# zynq.net
KiCad netlist of a schematic drawn in Altium Designer
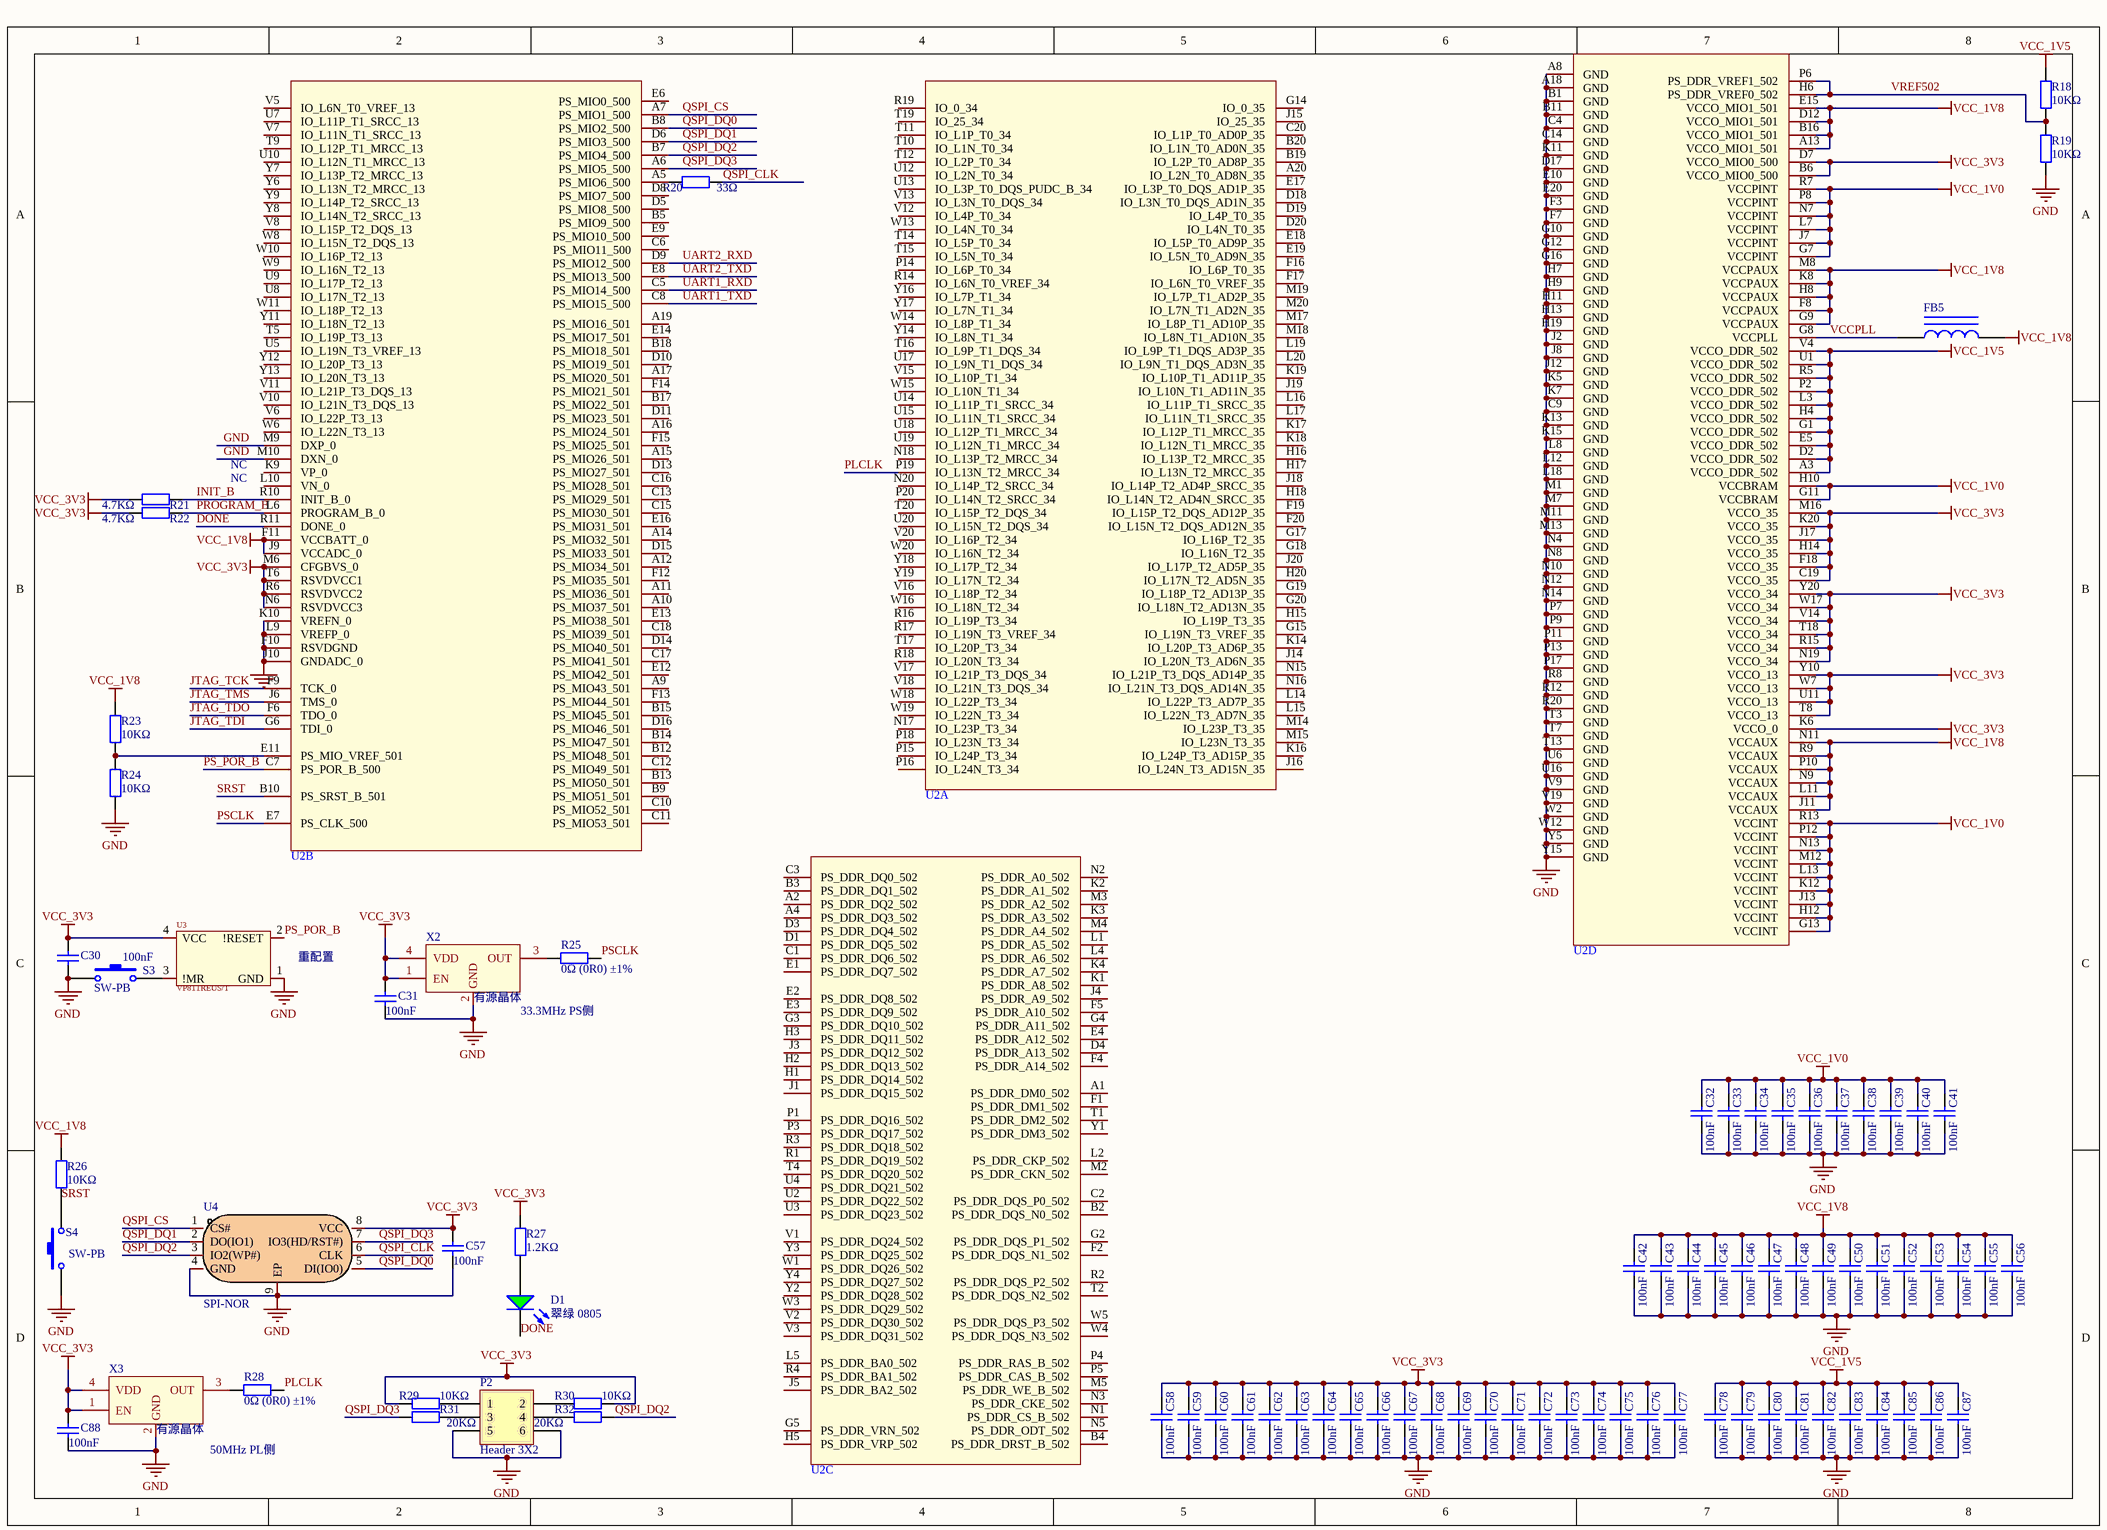
[diagram p0: zynq.SchDoc]

(export (version "E")
  (design (tool "Eeschema 10.0.6"))
  (components
    (comp (ref "C30")
      (value "100nF")
      (footprint "0805_C")
      (description "贴片电容")
      (libsource (lib "Miscellaneous Devices LC") (part "0402 100nF (104) 10% 16V"))
    )
    (comp (ref "C31")
      (value "100nF")
      (footprint "0805_C")
      (description "贴片电容")
      (libsource (lib "Miscellaneous Devices LC") (part "0402 100nF (104) 10% 16V"))
    )
    (comp (ref "C32")
      (value "100nF")
      (footprint "0201")
      (description "贴片电容")
      (libsource (lib "Miscellaneous Devices LC") (part "0402 100nF (104) 10% 16V"))
    )
    (comp (ref "C33")
      (value "100nF")
      (footprint "0201")
      (description "贴片电容")
      (libsource (lib "Miscellaneous Devices LC") (part "0402 100nF (104) 10% 16V"))
    )
    (comp (ref "C34")
      (value "100nF")
      (footprint "0201")
      (description "贴片电容")
      (libsource (lib "Miscellaneous Devices LC") (part "0402 100nF (104) 10% 16V"))
    )
    (comp (ref "C35")
      (value "100nF")
      (footprint "0201")
      (description "贴片电容")
      (libsource (lib "Miscellaneous Devices LC") (part "0402 100nF (104) 10% 16V"))
    )
    (comp (ref "C36")
      (value "100nF")
      (footprint "0201")
      (description "贴片电容")
      (libsource (lib "Miscellaneous Devices LC") (part "0402 100nF (104) 10% 16V"))
    )
    (comp (ref "C37")
      (value "100nF")
      (footprint "0201")
      (description "贴片电容")
      (libsource (lib "Miscellaneous Devices LC") (part "0402 100nF (104) 10% 16V"))
    )
    (comp (ref "C38")
      (value "100nF")
      (footprint "0201")
      (description "贴片电容")
      (libsource (lib "Miscellaneous Devices LC") (part "0402 100nF (104) 10% 16V"))
    )
    (comp (ref "C39")
      (value "100nF")
      (footprint "0201")
      (description "贴片电容")
      (libsource (lib "Miscellaneous Devices LC") (part "0402 100nF (104) 10% 16V"))
    )
    (comp (ref "C40")
      (value "100nF")
      (footprint "0201")
      (description "贴片电容")
      (libsource (lib "Miscellaneous Devices LC") (part "0402 100nF (104) 10% 16V"))
    )
    (comp (ref "C41")
      (value "100nF")
      (footprint "0201")
      (description "贴片电容")
      (libsource (lib "Miscellaneous Devices LC") (part "0402 100nF (104) 10% 16V"))
    )
    (comp (ref "C42")
      (value "100nF")
      (footprint "0201")
      (description "贴片电容")
      (libsource (lib "Miscellaneous Devices LC") (part "0402 100nF (104) 10% 16V"))
    )
    (comp (ref "C43")
      (value "100nF")
      (footprint "0201")
      (description "贴片电容")
      (libsource (lib "Miscellaneous Devices LC") (part "0402 100nF (104) 10% 16V"))
    )
    (comp (ref "C44")
      (value "100nF")
      (footprint "0201")
      (description "贴片电容")
      (libsource (lib "Miscellaneous Devices LC") (part "0402 100nF (104) 10% 16V"))
    )
    (comp (ref "C45")
      (value "100nF")
      (footprint "0201")
      (description "贴片电容")
      (libsource (lib "Miscellaneous Devices LC") (part "0402 100nF (104) 10% 16V"))
    )
    (comp (ref "C46")
      (value "100nF")
      (footprint "0201")
      (description "贴片电容")
      (libsource (lib "Miscellaneous Devices LC") (part "0402 100nF (104) 10% 16V"))
    )
    (comp (ref "C47")
      (value "100nF")
      (footprint "0201")
      (description "贴片电容")
      (libsource (lib "Miscellaneous Devices LC") (part "0402 100nF (104) 10% 16V"))
    )
    (comp (ref "C48")
      (value "100nF")
      (footprint "0201")
      (description "贴片电容")
      (libsource (lib "Miscellaneous Devices LC") (part "0402 100nF (104) 10% 16V"))
    )
    (comp (ref "C49")
      (value "100nF")
      (footprint "0201")
      (description "贴片电容")
      (libsource (lib "Miscellaneous Devices LC") (part "0402 100nF (104) 10% 16V"))
    )
    (comp (ref "C50")
      (value "100nF")
      (footprint "0201")
      (description "贴片电容")
      (libsource (lib "Miscellaneous Devices LC") (part "0402 100nF (104) 10% 16V"))
    )
    (comp (ref "C51")
      (value "100nF")
      (footprint "0201")
      (description "贴片电容")
      (libsource (lib "Miscellaneous Devices LC") (part "0402 100nF (104) 10% 16V"))
    )
    (comp (ref "C52")
      (value "100nF")
      (footprint "0201")
      (description "贴片电容")
      (libsource (lib "Miscellaneous Devices LC") (part "0402 100nF (104) 10% 16V"))
    )
    (comp (ref "C53")
      (value "100nF")
      (footprint "0201")
      (description "贴片电容")
      (libsource (lib "Miscellaneous Devices LC") (part "0402 100nF (104) 10% 16V"))
    )
    (comp (ref "C54")
      (value "100nF")
      (footprint "0201")
      (description "贴片电容")
      (libsource (lib "Miscellaneous Devices LC") (part "0402 100nF (104) 10% 16V"))
    )
    (comp (ref "C55")
      (value "100nF")
      (footprint "0201")
      (description "贴片电容")
      (libsource (lib "Miscellaneous Devices LC") (part "0402 100nF (104) 10% 16V"))
    )
    (comp (ref "C56")
      (value "100nF")
      (footprint "0201")
      (description "贴片电容")
      (libsource (lib "Miscellaneous Devices LC") (part "0402 100nF (104) 10% 16V"))
    )
    (comp (ref "C57")
      (value "100nF")
      (footprint "0402_C")
      (description "贴片电容")
      (libsource (lib "Miscellaneous Devices LC") (part "0402 100nF (104) 10% 16V"))
    )
    (comp (ref "C58")
      (value "100nF")
      (footprint "0201")
      (description "贴片电容")
      (libsource (lib "Miscellaneous Devices LC") (part "0402 100nF (104) 10% 16V"))
    )
    (comp (ref "C59")
      (value "100nF")
      (footprint "0201")
      (description "贴片电容")
      (libsource (lib "Miscellaneous Devices LC") (part "0402 100nF (104) 10% 16V"))
    )
    (comp (ref "C60")
      (value "100nF")
      (footprint "0201")
      (description "贴片电容")
      (libsource (lib "Miscellaneous Devices LC") (part "0402 100nF (104) 10% 16V"))
    )
    (comp (ref "C61")
      (value "100nF")
      (footprint "0201")
      (description "贴片电容")
      (libsource (lib "Miscellaneous Devices LC") (part "0402 100nF (104) 10% 16V"))
    )
    (comp (ref "C62")
      (value "100nF")
      (footprint "0201")
      (description "贴片电容")
      (libsource (lib "Miscellaneous Devices LC") (part "0402 100nF (104) 10% 16V"))
    )
    (comp (ref "C63")
      (value "100nF")
      (footprint "0201")
      (description "贴片电容")
      (libsource (lib "Miscellaneous Devices LC") (part "0402 100nF (104) 10% 16V"))
    )
    (comp (ref "C64")
      (value "100nF")
      (footprint "0201")
      (description "贴片电容")
      (libsource (lib "Miscellaneous Devices LC") (part "0402 100nF (104) 10% 16V"))
    )
    (comp (ref "C65")
      (value "100nF")
      (footprint "0201")
      (description "贴片电容")
      (libsource (lib "Miscellaneous Devices LC") (part "0402 100nF (104) 10% 16V"))
    )
    (comp (ref "C66")
      (value "100nF")
      (footprint "0201")
      (description "贴片电容")
      (libsource (lib "Miscellaneous Devices LC") (part "0402 100nF (104) 10% 16V"))
    )
    (comp (ref "C67")
      (value "100nF")
      (footprint "0201")
      (description "贴片电容")
      (libsource (lib "Miscellaneous Devices LC") (part "0402 100nF (104) 10% 16V"))
    )
    (comp (ref "C68")
      (value "100nF")
      (footprint "0201")
      (description "贴片电容")
      (libsource (lib "Miscellaneous Devices LC") (part "0402 100nF (104) 10% 16V"))
    )
    (comp (ref "C69")
      (value "100nF")
      (footprint "0201")
      (description "贴片电容")
      (libsource (lib "Miscellaneous Devices LC") (part "0402 100nF (104) 10% 16V"))
    )
    (comp (ref "C70")
      (value "100nF")
      (footprint "0201")
      (description "贴片电容")
      (libsource (lib "Miscellaneous Devices LC") (part "0402 100nF (104) 10% 16V"))
    )
    (comp (ref "C71")
      (value "100nF")
      (footprint "0201")
      (description "贴片电容")
      (libsource (lib "Miscellaneous Devices LC") (part "0402 100nF (104) 10% 16V"))
    )
    (comp (ref "C72")
      (value "100nF")
      (footprint "0201")
      (description "贴片电容")
      (libsource (lib "Miscellaneous Devices LC") (part "0402 100nF (104) 10% 16V"))
    )
    (comp (ref "C73")
      (value "100nF")
      (footprint "0201")
      (description "贴片电容")
      (libsource (lib "Miscellaneous Devices LC") (part "0402 100nF (104) 10% 16V"))
    )
    (comp (ref "C74")
      (value "100nF")
      (footprint "0201")
      (description "贴片电容")
      (libsource (lib "Miscellaneous Devices LC") (part "0402 100nF (104) 10% 16V"))
    )
    (comp (ref "C75")
      (value "100nF")
      (footprint "0201")
      (description "贴片电容")
      (libsource (lib "Miscellaneous Devices LC") (part "0402 100nF (104) 10% 16V"))
    )
    (comp (ref "C76")
      (value "100nF")
      (footprint "0201")
      (description "贴片电容")
      (libsource (lib "Miscellaneous Devices LC") (part "0402 100nF (104) 10% 16V"))
    )
    (comp (ref "C77")
      (value "100nF")
      (footprint "0201")
      (description "贴片电容")
      (libsource (lib "Miscellaneous Devices LC") (part "0402 100nF (104) 10% 16V"))
    )
    (comp (ref "C78")
      (value "100nF")
      (footprint "0201")
      (description "贴片电容")
      (libsource (lib "Miscellaneous Devices LC") (part "0402 100nF (104) 10% 16V"))
    )
    (comp (ref "C79")
      (value "100nF")
      (footprint "0201")
      (description "贴片电容")
      (libsource (lib "Miscellaneous Devices LC") (part "0402 100nF (104) 10% 16V"))
    )
    (comp (ref "C80")
      (value "100nF")
      (footprint "0201")
      (description "贴片电容")
      (libsource (lib "Miscellaneous Devices LC") (part "0402 100nF (104) 10% 16V"))
    )
    (comp (ref "C81")
      (value "100nF")
      (footprint "0201")
      (description "贴片电容")
      (libsource (lib "Miscellaneous Devices LC") (part "0402 100nF (104) 10% 16V"))
    )
    (comp (ref "C82")
      (value "100nF")
      (footprint "0201")
      (description "贴片电容")
      (libsource (lib "Miscellaneous Devices LC") (part "0402 100nF (104) 10% 16V"))
    )
    (comp (ref "C83")
      (value "100nF")
      (footprint "0201")
      (description "贴片电容")
      (libsource (lib "Miscellaneous Devices LC") (part "0402 100nF (104) 10% 16V"))
    )
    (comp (ref "C84")
      (value "100nF")
      (footprint "0201")
      (description "贴片电容")
      (libsource (lib "Miscellaneous Devices LC") (part "0402 100nF (104) 10% 16V"))
    )
    (comp (ref "C85")
      (value "100nF")
      (footprint "0201")
      (description "贴片电容")
      (libsource (lib "Miscellaneous Devices LC") (part "0402 100nF (104) 10% 16V"))
    )
    (comp (ref "C86")
      (value "100nF")
      (footprint "0201")
      (description "贴片电容")
      (libsource (lib "Miscellaneous Devices LC") (part "0402 100nF (104) 10% 16V"))
    )
    (comp (ref "C87")
      (value "100nF")
      (footprint "0201")
      (description "贴片电容")
      (libsource (lib "Miscellaneous Devices LC") (part "0402 100nF (104) 10% 16V"))
    )
    (comp (ref "C88")
      (value "100nF")
      (footprint "0805_C")
      (description "贴片电容")
      (libsource (lib "Miscellaneous Devices LC") (part "0402 100nF (104) 10% 16V"))
    )
    (comp (ref "D1")
      (value "翠绿 0805")
      (footprint "0805_LED_S1")
      (description "发光二极管")
      (libsource (lib "Miscellaneous Devices LC") (part "0805 翠绿"))
    )
    (comp (ref "FB5")
      (value "100Ω ±25% 100MHz")
      (footprint "0805_L")
      (description "贴片磁珠")
      (libsource (lib "Miscellaneous Devices LC") (part "0805 100Ω 25% 100MHz"))
    )
    (comp (ref "P2")
      (value "Header 3X2")
      (footprint "HDR2X3")
      (description "Header, 3-Pin, Dual row")
      (fields (field (name "PUBLISHER") "Altium Limited"))
      (libsource (lib "Miscellaneous Connectors") (part "Header 3X2"))
    )
    (comp (ref "R18")
      (value "10KΩ")
      (footprint "0805_R")
      (description "贴片电阻")
      (libsource (lib "Miscellaneous Devices LC") (part "0805 10KΩ (1002) 1%"))
    )
    (comp (ref "R19")
      (value "10KΩ")
      (footprint "0805_R")
      (description "贴片电阻")
      (libsource (lib "Miscellaneous Devices LC") (part "0805 10KΩ (1002) 1%"))
    )
    (comp (ref "R20")
      (value "33Ω")
      (footprint "0402_R")
      (description "贴片电阻")
      (libsource (lib "Miscellaneous Devices LC") (part "0402 33Ω (33R0) 1%"))
    )
    (comp (ref "R21")
      (value "4.7KΩ")
      (footprint "0805_R")
      (description "贴片电阻")
      (libsource (lib "Miscellaneous Devices LC") (part "0402 4.7KΩ (4701) 1%"))
    )
    (comp (ref "R22")
      (value "4.7KΩ")
      (footprint "0805_R")
      (description "贴片电阻")
      (libsource (lib "Miscellaneous Devices LC") (part "0402 4.7KΩ (4701) 1%"))
    )
    (comp (ref "R23")
      (value "10KΩ")
      (footprint "0805_R")
      (description "贴片电阻")
      (libsource (lib "Miscellaneous Devices LC") (part "0805 10KΩ (1002) 1%"))
    )
    (comp (ref "R24")
      (value "10KΩ")
      (footprint "0805_R")
      (description "贴片电阻")
      (libsource (lib "Miscellaneous Devices LC") (part "0805 10KΩ (1002) 1%"))
    )
    (comp (ref "R25")
      (value "0Ω (0R0) ±1%")
      (footprint "0805_R")
      (description "贴片电阻")
      (libsource (lib "Miscellaneous Devices LC") (part "0805 0Ω (0R0) 1%"))
    )
    (comp (ref "R26")
      (value "10KΩ")
      (footprint "0805_R")
      (description "贴片电阻")
      (libsource (lib "") (part "0402 10KΩ (1002) 1%_1"))
    )
    (comp (ref "R27")
      (value "1.2KΩ")
      (footprint "0805_R")
      (description "贴片电阻")
      (libsource (lib "Miscellaneous Devices LC") (part "0805 1.2KΩ (1201) 1%"))
    )
    (comp (ref "R28")
      (value "0Ω (0R0) ±1%")
      (footprint "0805_R")
      (description "贴片电阻")
      (libsource (lib "Miscellaneous Devices LC") (part "0805 0Ω (0R0) 1%"))
    )
    (comp (ref "R29")
      (value "10KΩ")
      (footprint "0402_R")
      (description "贴片电阻")
      (libsource (lib "Miscellaneous Devices LC") (part "0402 10KΩ (1002) 1%"))
    )
    (comp (ref "R30")
      (value "10KΩ")
      (footprint "0402_R")
      (description "贴片电阻")
      (libsource (lib "Miscellaneous Devices LC") (part "0402 10KΩ (1002) 1%"))
    )
    (comp (ref "R31")
      (value "20KΩ")
      (footprint "0402_R")
      (description "贴片电阻")
      (libsource (lib "Miscellaneous Devices LC") (part "0402 20KΩ (2002) 1%"))
    )
    (comp (ref "R32")
      (value "20KΩ")
      (footprint "0402_R")
      (description "贴片电阻")
      (libsource (lib "Miscellaneous Devices LC") (part "0402 20KΩ (2002) 1%"))
    )
    (comp (ref "S3")
      (value "SW-PB")
      (footprint "SW-3*4-2P")
      (description "Switch")
      (fields (field (name "PUBLISHER") "Altium Limited"))
      (libsource (lib "Miscellaneous Devices") (part "SW-PB"))
    )
    (comp (ref "S4")
      (value "SW-PB")
      (footprint "SW-3*4-2P")
      (description "Switch")
      (fields (field (name "PUBLISHER") "Altium Limited"))
      (libsource (lib "Miscellaneous Devices") (part "SW-PB"))
    )
    (comp (ref "U2")
      (value "XC7Z020-2CLG400I")
      (footprint "FBGA-400_L17.0-W17.0-R20-C20-P0.80-TL")
      (fields (field (name "MANUFACTURER") "XILINX(赛灵思)"))
      (libsource (lib "五向开关") (part "XC7Z020-2CLG400I"))
    )
    (comp (ref "U3")
      (value "VP811REUS/T")
      (footprint "SOT-143_L2.9-W1.3-P1.92-LS2.3-BL")
      (description "复位电平管理芯片")
      (fields (field (name "MANUFACTURER") "VP(中芯集成)"))
      (libsource (lib "五向开关") (part "VP811REUS/T"))
    )
    (comp (ref "U4")
      (value "SPI-NOR")
      (footprint "WSON8")
      (description "NOR FLASH")
      (libsource (lib "五向开关") (part "W25Q64"))
    )
    (comp (ref "X2")
      (value "有源晶体")
      (footprint "3225")
      (description "有源晶振")
      (libsource (lib "五向开关") (part "有源晶体"))
    )
    (comp (ref "X3")
      (value "有源晶体")
      (footprint "3225")
      (description "有源晶振")
      (libsource (lib "五向开关") (part "有源晶体"))
    )
  )
  (nets
    (net (code "1") (name "/DONE") (class "Default")
      (node (ref "D1") (pin "K") (pinfunction "K_K") (pintype "passive"))
      (node (ref "U2") (pin "R11") (pinfunction "DONE_0_R11") (pintype "passive"))
    )
    (net (code "2") (name "/INIT_B") (class "Default")
      (node (ref "R21") (pin "2") (pinfunction "2_2") (pintype "passive"))
      (node (ref "U2") (pin "R10") (pinfunction "INIT_B_0_R10") (pintype "passive"))
    )
    (net (code "3") (name "/JTAG_TCK") (class "Default")
      (node (ref "U2") (pin "F9") (pinfunction "TCK_0_F9") (pintype "passive"))
    )
    (net (code "4") (name "/JTAG_TDI") (class "Default")
      (node (ref "U2") (pin "G6") (pinfunction "TDI_0_G6") (pintype "passive"))
    )
    (net (code "5") (name "/JTAG_TDO") (class "Default")
      (node (ref "U2") (pin "F6") (pinfunction "TDO_0_F6") (pintype "passive"))
    )
    (net (code "6") (name "/JTAG_TMS") (class "Default")
      (node (ref "U2") (pin "J6") (pinfunction "TMS_0_J6") (pintype "passive"))
    )
    (net (code "7") (name "/PLCLK") (class "Default")
      (node (ref "R28") (pin "2") (pinfunction "2_2") (pintype "passive"))
      (node (ref "U2") (pin "P19") (pinfunction "IO_L13N_T2_MRCC_34_P19") (pintype "passive"))
    )
    (net (code "8") (name "/PROGRAM_B") (class "Default")
      (node (ref "R22") (pin "2") (pinfunction "2_2") (pintype "passive"))
      (node (ref "U2") (pin "L6") (pinfunction "PROGRAM_B_0_L6") (pintype "passive"))
    )
    (net (code "9") (name "/PSCLK") (class "Default")
      (node (ref "R25") (pin "2") (pinfunction "2_2") (pintype "passive"))
      (node (ref "U2") (pin "E7") (pinfunction "PS_CLK_500_E7") (pintype "passive"))
    )
    (net (code "10") (name "/PS_POR_B") (class "Default")
      (node (ref "U2") (pin "C7") (pinfunction "PS_POR_B_500_C7") (pintype "passive"))
      (node (ref "U3") (pin "2") (pinfunction "!RESET_2") (pintype "passive"))
    )
    (net (code "11") (name "/QSPI_CLK") (class "Default")
      (node (ref "R20") (pin "2") (pinfunction "2_2") (pintype "passive"))
      (node (ref "U4") (pin "6") (pinfunction "CLK_6") (pintype "passive"))
    )
    (net (code "12") (name "/QSPI_CS") (class "Default")
      (node (ref "U2") (pin "A7") (pinfunction "PS_MIO1_500_A7") (pintype "passive"))
      (node (ref "U4") (pin "1") (pinfunction "CS#_1") (pintype "passive"))
    )
    (net (code "13") (name "/QSPI_DQ0") (class "Default")
      (node (ref "U2") (pin "B8") (pinfunction "PS_MIO2_500_B8") (pintype "passive"))
      (node (ref "U4") (pin "5") (pinfunction "DI(IO0)_5") (pintype "passive"))
    )
    (net (code "14") (name "/QSPI_DQ1") (class "Default")
      (node (ref "U2") (pin "D6") (pinfunction "PS_MIO3_500_D6") (pintype "passive"))
      (node (ref "U4") (pin "2") (pinfunction "DO(IO1)_2") (pintype "passive"))
    )
    (net (code "15") (name "/QSPI_DQ2") (class "Default")
      (node (ref "R32") (pin "2") (pinfunction "2_2") (pintype "passive"))
      (node (ref "U2") (pin "B7") (pinfunction "PS_MIO4_500_B7") (pintype "passive"))
      (node (ref "U4") (pin "3") (pinfunction "IO2(WP#)_3") (pintype "passive"))
    )
    (net (code "16") (name "/QSPI_DQ3") (class "Default")
      (node (ref "R31") (pin "1") (pinfunction "1_1") (pintype "passive"))
      (node (ref "U2") (pin "A6") (pinfunction "PS_MIO5_500_A6") (pintype "passive"))
      (node (ref "U4") (pin "7") (pinfunction "IO3(HD/RST#)_7") (pintype "passive"))
    )
    (net (code "17") (name "/SRST") (class "Default")
      (node (ref "R26") (pin "1") (pinfunction "1_1") (pintype "passive"))
      (node (ref "S4") (pin "2") (pinfunction "2_2") (pintype "passive"))
      (node (ref "U2") (pin "B10") (pinfunction "PS_SRST_B_501_B10") (pintype "passive"))
    )
    (net (code "18") (name "/UART1_RXD") (class "Default")
      (node (ref "U2") (pin "C5") (pinfunction "PS_MIO14_500_C5") (pintype "passive"))
    )
    (net (code "19") (name "/UART1_TXD") (class "Default")
      (node (ref "U2") (pin "C8") (pinfunction "PS_MIO15_500_C8") (pintype "passive"))
    )
    (net (code "20") (name "/UART2_RXD") (class "Default")
      (node (ref "U2") (pin "D9") (pinfunction "PS_MIO12_500_D9") (pintype "passive"))
    )
    (net (code "21") (name "/UART2_TXD") (class "Default")
      (node (ref "U2") (pin "E8") (pinfunction "PS_MIO13_500_E8") (pintype "passive"))
    )
    (net (code "22") (name "/VCCPLL") (class "Default")
      (node (ref "FB5") (pin "1") (pinfunction "1_1") (pintype "passive"))
      (node (ref "U2") (pin "G8") (pinfunction "VCCPLL_G8") (pintype "passive"))
    )
    (net (code "23") (name "/VREF502") (class "Default")
      (node (ref "R18") (pin "1") (pinfunction "1_1") (pintype "passive"))
      (node (ref "R19") (pin "2") (pinfunction "2_2") (pintype "passive"))
      (node (ref "U2") (pin "H6") (pinfunction "PS_DDR_VREF0_502_H6") (pintype "passive"))
      (node (ref "U2") (pin "P6") (pinfunction "PS_DDR_VREF1_502_P6") (pintype "passive"))
    )
    (net (code "24") (name "GND") (class "Default")
      (node (ref "C30") (pin "1") (pinfunction "1_1") (pintype "passive"))
      (node (ref "C31") (pin "1") (pinfunction "1_1") (pintype "passive"))
      (node (ref "C32") (pin "1") (pinfunction "1_1") (pintype "passive"))
      (node (ref "C33") (pin "1") (pinfunction "1_1") (pintype "passive"))
      (node (ref "C34") (pin "1") (pinfunction "1_1") (pintype "passive"))
      (node (ref "C35") (pin "1") (pinfunction "1_1") (pintype "passive"))
      (node (ref "C36") (pin "1") (pinfunction "1_1") (pintype "passive"))
      (node (ref "C37") (pin "1") (pinfunction "1_1") (pintype "passive"))
      (node (ref "C38") (pin "1") (pinfunction "1_1") (pintype "passive"))
      (node (ref "C39") (pin "1") (pinfunction "1_1") (pintype "passive"))
      (node (ref "C40") (pin "1") (pinfunction "1_1") (pintype "passive"))
      (node (ref "C41") (pin "1") (pinfunction "1_1") (pintype "passive"))
      (node (ref "C42") (pin "1") (pinfunction "1_1") (pintype "passive"))
      (node (ref "C43") (pin "1") (pinfunction "1_1") (pintype "passive"))
      (node (ref "C44") (pin "1") (pinfunction "1_1") (pintype "passive"))
      (node (ref "C45") (pin "1") (pinfunction "1_1") (pintype "passive"))
      (node (ref "C46") (pin "1") (pinfunction "1_1") (pintype "passive"))
      (node (ref "C47") (pin "1") (pinfunction "1_1") (pintype "passive"))
      (node (ref "C48") (pin "1") (pinfunction "1_1") (pintype "passive"))
      (node (ref "C49") (pin "1") (pinfunction "1_1") (pintype "passive"))
      (node (ref "C50") (pin "1") (pinfunction "1_1") (pintype "passive"))
      (node (ref "C51") (pin "1") (pinfunction "1_1") (pintype "passive"))
      (node (ref "C52") (pin "1") (pinfunction "1_1") (pintype "passive"))
      (node (ref "C53") (pin "1") (pinfunction "1_1") (pintype "passive"))
      (node (ref "C54") (pin "1") (pinfunction "1_1") (pintype "passive"))
      (node (ref "C55") (pin "1") (pinfunction "1_1") (pintype "passive"))
      (node (ref "C56") (pin "1") (pinfunction "1_1") (pintype "passive"))
      (node (ref "C57") (pin "1") (pinfunction "1_1") (pintype "passive"))
      (node (ref "C58") (pin "1") (pinfunction "1_1") (pintype "passive"))
      (node (ref "C59") (pin "1") (pinfunction "1_1") (pintype "passive"))
      (node (ref "C60") (pin "1") (pinfunction "1_1") (pintype "passive"))
      (node (ref "C61") (pin "1") (pinfunction "1_1") (pintype "passive"))
      (node (ref "C62") (pin "1") (pinfunction "1_1") (pintype "passive"))
      (node (ref "C63") (pin "1") (pinfunction "1_1") (pintype "passive"))
      (node (ref "C64") (pin "1") (pinfunction "1_1") (pintype "passive"))
      (node (ref "C65") (pin "1") (pinfunction "1_1") (pintype "passive"))
      (node (ref "C66") (pin "1") (pinfunction "1_1") (pintype "passive"))
      (node (ref "C67") (pin "1") (pinfunction "1_1") (pintype "passive"))
      (node (ref "C68") (pin "1") (pinfunction "1_1") (pintype "passive"))
      (node (ref "C69") (pin "1") (pinfunction "1_1") (pintype "passive"))
      (node (ref "C70") (pin "1") (pinfunction "1_1") (pintype "passive"))
      (node (ref "C71") (pin "1") (pinfunction "1_1") (pintype "passive"))
      (node (ref "C72") (pin "1") (pinfunction "1_1") (pintype "passive"))
      (node (ref "C73") (pin "1") (pinfunction "1_1") (pintype "passive"))
      (node (ref "C74") (pin "1") (pinfunction "1_1") (pintype "passive"))
      (node (ref "C75") (pin "1") (pinfunction "1_1") (pintype "passive"))
      (node (ref "C76") (pin "1") (pinfunction "1_1") (pintype "passive"))
      (node (ref "C77") (pin "1") (pinfunction "1_1") (pintype "passive"))
      (node (ref "C78") (pin "1") (pinfunction "1_1") (pintype "passive"))
      (node (ref "C79") (pin "1") (pinfunction "1_1") (pintype "passive"))
      (node (ref "C80") (pin "1") (pinfunction "1_1") (pintype "passive"))
      (node (ref "C81") (pin "1") (pinfunction "1_1") (pintype "passive"))
      (node (ref "C82") (pin "1") (pinfunction "1_1") (pintype "passive"))
      (node (ref "C83") (pin "1") (pinfunction "1_1") (pintype "passive"))
      (node (ref "C84") (pin "1") (pinfunction "1_1") (pintype "passive"))
      (node (ref "C85") (pin "1") (pinfunction "1_1") (pintype "passive"))
      (node (ref "C86") (pin "1") (pinfunction "1_1") (pintype "passive"))
      (node (ref "C87") (pin "1") (pinfunction "1_1") (pintype "passive"))
      (node (ref "C88") (pin "1") (pinfunction "1_1") (pintype "passive"))
      (node (ref "P2") (pin "5") (pinfunction "5_5") (pintype "passive"))
      (node (ref "P2") (pin "6") (pinfunction "6_6") (pintype "passive"))
      (node (ref "R19") (pin "1") (pinfunction "1_1") (pintype "passive"))
      (node (ref "R24") (pin "1") (pinfunction "1_1") (pintype "passive"))
      (node (ref "S3") (pin "1") (pinfunction "1_1") (pintype "passive"))
      (node (ref "S4") (pin "1") (pinfunction "1_1") (pintype "passive"))
      (node (ref "U2") (pin "A18") (pinfunction "GND_A18") (pintype "passive"))
      (node (ref "U2") (pin "A8") (pinfunction "GND_A8") (pintype "passive"))
      (node (ref "U2") (pin "B1") (pinfunction "GND_B1") (pintype "passive"))
      (node (ref "U2") (pin "B11") (pinfunction "GND_B11") (pintype "passive"))
      (node (ref "U2") (pin "C14") (pinfunction "GND_C14") (pintype "passive"))
      (node (ref "U2") (pin "C4") (pinfunction "GND_C4") (pintype "passive"))
      (node (ref "U2") (pin "C9") (pinfunction "GND_C9") (pintype "passive"))
      (node (ref "U2") (pin "D17") (pinfunction "GND_D17") (pintype "passive"))
      (node (ref "U2") (pin "E10") (pinfunction "GND_E10") (pintype "passive"))
      (node (ref "U2") (pin "E20") (pinfunction "GND_E20") (pintype "passive"))
      (node (ref "U2") (pin "F10") (pinfunction "RSVDGND_F10") (pintype "passive"))
      (node (ref "U2") (pin "F3") (pinfunction "GND_F3") (pintype "passive"))
      (node (ref "U2") (pin "F7") (pinfunction "GND_F7") (pintype "passive"))
      (node (ref "U2") (pin "G10") (pinfunction "GND_G10") (pintype "passive"))
      (node (ref "U2") (pin "G12") (pinfunction "GND_G12") (pintype "passive"))
      (node (ref "U2") (pin "G16") (pinfunction "GND_G16") (pintype "passive"))
      (node (ref "U2") (pin "H11") (pinfunction "GND_H11") (pintype "passive"))
      (node (ref "U2") (pin "H13") (pinfunction "GND_H13") (pintype "passive"))
      (node (ref "U2") (pin "H19") (pinfunction "GND_H19") (pintype "passive"))
      (node (ref "U2") (pin "H7") (pinfunction "GND_H7") (pintype "passive"))
      (node (ref "U2") (pin "H9") (pinfunction "GND_H9") (pintype "passive"))
      (node (ref "U2") (pin "J10") (pinfunction "GNDADC_0_J10") (pintype "passive"))
      (node (ref "U2") (pin "J12") (pinfunction "GND_J12") (pintype "passive"))
      (node (ref "U2") (pin "J2") (pinfunction "GND_J2") (pintype "passive"))
      (node (ref "U2") (pin "J8") (pinfunction "GND_J8") (pintype "passive"))
      (node (ref "U2") (pin "K10") (pinfunction "VREFN_0_K10") (pintype "passive"))
      (node (ref "U2") (pin "K11") (pinfunction "GND_K11") (pintype "passive"))
      (node (ref "U2") (pin "K13") (pinfunction "GND_K13") (pintype "passive"))
      (node (ref "U2") (pin "K15") (pinfunction "GND_K15") (pintype "passive"))
      (node (ref "U2") (pin "K5") (pinfunction "GND_K5") (pintype "passive"))
      (node (ref "U2") (pin "K7") (pinfunction "GND_K7") (pintype "passive"))
      (node (ref "U2") (pin "L12") (pinfunction "GND_L12") (pintype "passive"))
      (node (ref "U2") (pin "L18") (pinfunction "GND_L18") (pintype "passive"))
      (node (ref "U2") (pin "L8") (pinfunction "GND_L8") (pintype "passive"))
      (node (ref "U2") (pin "L9") (pinfunction "VREFP_0_L9") (pintype "passive"))
      (node (ref "U2") (pin "M1") (pinfunction "GND_M1") (pintype "passive"))
      (node (ref "U2") (pin "M10") (pinfunction "DXN_0_M10") (pintype "passive"))
      (node (ref "U2") (pin "M11") (pinfunction "GND_M11") (pintype "passive"))
      (node (ref "U2") (pin "M13") (pinfunction "GND_M13") (pintype "passive"))
      (node (ref "U2") (pin "M7") (pinfunction "GND_M7") (pintype "passive"))
      (node (ref "U2") (pin "M9") (pinfunction "DXP_0_M9") (pintype "passive"))
      (node (ref "U2") (pin "N10") (pinfunction "GND_N10") (pintype "passive"))
      (node (ref "U2") (pin "N12") (pinfunction "GND_N12") (pintype "passive"))
      (node (ref "U2") (pin "N14") (pinfunction "GND_N14") (pintype "passive"))
      (node (ref "U2") (pin "N4") (pinfunction "GND_N4") (pintype "passive"))
      (node (ref "U2") (pin "N8") (pinfunction "GND_N8") (pintype "passive"))
      (node (ref "U2") (pin "P11") (pinfunction "GND_P11") (pintype "passive"))
      (node (ref "U2") (pin "P13") (pinfunction "GND_P13") (pintype "passive"))
      (node (ref "U2") (pin "P17") (pinfunction "GND_P17") (pintype "passive"))
      (node (ref "U2") (pin "P7") (pinfunction "GND_P7") (pintype "passive"))
      (node (ref "U2") (pin "P9") (pinfunction "GND_P9") (pintype "passive"))
      (node (ref "U2") (pin "R12") (pinfunction "GND_R12") (pintype "passive"))
      (node (ref "U2") (pin "R20") (pinfunction "GND_R20") (pintype "passive"))
      (node (ref "U2") (pin "R8") (pinfunction "GND_R8") (pintype "passive"))
      (node (ref "U2") (pin "T13") (pinfunction "GND_T13") (pintype "passive"))
      (node (ref "U2") (pin "T3") (pinfunction "GND_T3") (pintype "passive"))
      (node (ref "U2") (pin "T7") (pinfunction "GND_T7") (pintype "passive"))
      (node (ref "U2") (pin "U16") (pinfunction "GND_U16") (pintype "passive"))
      (node (ref "U2") (pin "U6") (pinfunction "GND_U6") (pintype "passive"))
      (node (ref "U2") (pin "V19") (pinfunction "GND_V19") (pintype "passive"))
      (node (ref "U2") (pin "V9") (pinfunction "GND_V9") (pintype "passive"))
      (node (ref "U2") (pin "W12") (pinfunction "GND_W12") (pintype "passive"))
      (node (ref "U2") (pin "W2") (pinfunction "GND_W2") (pintype "passive"))
      (node (ref "U2") (pin "Y15") (pinfunction "GND_Y15") (pintype "passive"))
      (node (ref "U2") (pin "Y5") (pinfunction "GND_Y5") (pintype "passive"))
      (node (ref "U3") (pin "1") (pinfunction "GND_1") (pintype "passive"))
      (node (ref "U4") (pin "4") (pinfunction "GND_4") (pintype "passive"))
      (node (ref "U4") (pin "9") (pinfunction "EP_9") (pintype "passive"))
      (node (ref "X2") (pin "2") (pinfunction "GND_2") (pintype "passive"))
      (node (ref "X3") (pin "2") (pinfunction "GND_2") (pintype "passive"))
    )
    (net (code "25") (name "Net-(D1-PadA)") (class "Default")
      (node (ref "D1") (pin "A") (pinfunction "A_A") (pintype "passive"))
      (node (ref "R27") (pin "1") (pinfunction "1_1") (pintype "passive"))
    )
    (net (code "26") (name "Net-(P2-Pad1)") (class "Default")
      (node (ref "P2") (pin "1") (pinfunction "1_1") (pintype "passive"))
      (node (ref "R29") (pin "2") (pinfunction "2_2") (pintype "passive"))
    )
    (net (code "27") (name "Net-(P2-Pad2)") (class "Default")
      (node (ref "P2") (pin "2") (pinfunction "2_2") (pintype "passive"))
      (node (ref "R30") (pin "1") (pinfunction "1_1") (pintype "passive"))
    )
    (net (code "28") (name "Net-(P2-Pad3)") (class "Default")
      (node (ref "P2") (pin "3") (pinfunction "3_3") (pintype "passive"))
      (node (ref "R31") (pin "2") (pinfunction "2_2") (pintype "passive"))
    )
    (net (code "29") (name "Net-(P2-Pad4)") (class "Default")
      (node (ref "P2") (pin "4") (pinfunction "4_4") (pintype "passive"))
      (node (ref "R32") (pin "1") (pinfunction "1_1") (pintype "passive"))
    )
    (net (code "30") (name "Net-(U2B-PS_MIO6_500)") (class "Default")
      (node (ref "R20") (pin "1") (pinfunction "1_1") (pintype "passive"))
      (node (ref "U2") (pin "A5") (pinfunction "PS_MIO6_500_A5") (pintype "passive"))
    )
    (net (code "31") (name "Net-(U2B-PS_MIO_VREF_501)") (class "Default")
      (node (ref "R23") (pin "1") (pinfunction "1_1") (pintype "passive"))
      (node (ref "R24") (pin "2") (pinfunction "2_2") (pintype "passive"))
      (node (ref "U2") (pin "E11") (pinfunction "PS_MIO_VREF_501_E11") (pintype "passive"))
    )
    (net (code "32") (name "Net-(U3-!MR)") (class "Default")
      (node (ref "S3") (pin "2") (pinfunction "2_2") (pintype "passive"))
      (node (ref "U3") (pin "3") (pinfunction "!MR_3") (pintype "passive"))
    )
    (net (code "33") (name "Net-(X2-OUT)") (class "Default")
      (node (ref "R25") (pin "1") (pinfunction "1_1") (pintype "passive"))
      (node (ref "X2") (pin "3") (pinfunction "OUT_3") (pintype "passive"))
    )
    (net (code "34") (name "Net-(X3-OUT)") (class "Default")
      (node (ref "R28") (pin "1") (pinfunction "1_1") (pintype "passive"))
      (node (ref "X3") (pin "3") (pinfunction "OUT_3") (pintype "passive"))
    )
    (net (code "35") (name "VCC_1V0") (class "Default")
      (node (ref "C32") (pin "2") (pinfunction "2_2") (pintype "passive"))
      (node (ref "C33") (pin "2") (pinfunction "2_2") (pintype "passive"))
      (node (ref "C34") (pin "2") (pinfunction "2_2") (pintype "passive"))
      (node (ref "C35") (pin "2") (pinfunction "2_2") (pintype "passive"))
      (node (ref "C36") (pin "2") (pinfunction "2_2") (pintype "passive"))
      (node (ref "C37") (pin "2") (pinfunction "2_2") (pintype "passive"))
      (node (ref "C38") (pin "2") (pinfunction "2_2") (pintype "passive"))
      (node (ref "C39") (pin "2") (pinfunction "2_2") (pintype "passive"))
      (node (ref "C40") (pin "2") (pinfunction "2_2") (pintype "passive"))
      (node (ref "C41") (pin "2") (pinfunction "2_2") (pintype "passive"))
      (node (ref "U2") (pin "G11") (pinfunction "VCCBRAM_G11") (pintype "passive"))
      (node (ref "U2") (pin "G13") (pinfunction "VCCINT_G13") (pintype "passive"))
      (node (ref "U2") (pin "G7") (pinfunction "VCCPINT_G7") (pintype "passive"))
      (node (ref "U2") (pin "H10") (pinfunction "VCCBRAM_H10") (pintype "passive"))
      (node (ref "U2") (pin "H12") (pinfunction "VCCINT_H12") (pintype "passive"))
      (node (ref "U2") (pin "J13") (pinfunction "VCCINT_J13") (pintype "passive"))
      (node (ref "U2") (pin "J7") (pinfunction "VCCPINT_J7") (pintype "passive"))
      (node (ref "U2") (pin "K12") (pinfunction "VCCINT_K12") (pintype "passive"))
      (node (ref "U2") (pin "L13") (pinfunction "VCCINT_L13") (pintype "passive"))
      (node (ref "U2") (pin "L7") (pinfunction "VCCPINT_L7") (pintype "passive"))
      (node (ref "U2") (pin "M12") (pinfunction "VCCINT_M12") (pintype "passive"))
      (node (ref "U2") (pin "N13") (pinfunction "VCCINT_N13") (pintype "passive"))
      (node (ref "U2") (pin "N7") (pinfunction "VCCPINT_N7") (pintype "passive"))
      (node (ref "U2") (pin "P12") (pinfunction "VCCINT_P12") (pintype "passive"))
      (node (ref "U2") (pin "P8") (pinfunction "VCCPINT_P8") (pintype "passive"))
      (node (ref "U2") (pin "R13") (pinfunction "VCCINT_R13") (pintype "passive"))
      (node (ref "U2") (pin "R7") (pinfunction "VCCPINT_R7") (pintype "passive"))
    )
    (net (code "36") (name "VCC_1V5") (class "Default")
      (node (ref "C78") (pin "2") (pinfunction "2_2") (pintype "passive"))
      (node (ref "C79") (pin "2") (pinfunction "2_2") (pintype "passive"))
      (node (ref "C80") (pin "2") (pinfunction "2_2") (pintype "passive"))
      (node (ref "C81") (pin "2") (pinfunction "2_2") (pintype "passive"))
      (node (ref "C82") (pin "2") (pinfunction "2_2") (pintype "passive"))
      (node (ref "C83") (pin "2") (pinfunction "2_2") (pintype "passive"))
      (node (ref "C84") (pin "2") (pinfunction "2_2") (pintype "passive"))
      (node (ref "C85") (pin "2") (pinfunction "2_2") (pintype "passive"))
      (node (ref "C86") (pin "2") (pinfunction "2_2") (pintype "passive"))
      (node (ref "C87") (pin "2") (pinfunction "2_2") (pintype "passive"))
      (node (ref "R18") (pin "2") (pinfunction "2_2") (pintype "passive"))
      (node (ref "U2") (pin "A3") (pinfunction "VCCO_DDR_502_A3") (pintype "passive"))
      (node (ref "U2") (pin "D2") (pinfunction "VCCO_DDR_502_D2") (pintype "passive"))
      (node (ref "U2") (pin "E5") (pinfunction "VCCO_DDR_502_E5") (pintype "passive"))
      (node (ref "U2") (pin "G1") (pinfunction "VCCO_DDR_502_G1") (pintype "passive"))
      (node (ref "U2") (pin "H4") (pinfunction "VCCO_DDR_502_H4") (pintype "passive"))
      (node (ref "U2") (pin "L3") (pinfunction "VCCO_DDR_502_L3") (pintype "passive"))
      (node (ref "U2") (pin "P2") (pinfunction "VCCO_DDR_502_P2") (pintype "passive"))
      (node (ref "U2") (pin "R5") (pinfunction "VCCO_DDR_502_R5") (pintype "passive"))
      (node (ref "U2") (pin "U1") (pinfunction "VCCO_DDR_502_U1") (pintype "passive"))
      (node (ref "U2") (pin "V4") (pinfunction "VCCO_DDR_502_V4") (pintype "passive"))
    )
    (net (code "37") (name "VCC_1V8") (class "Default")
      (node (ref "C42") (pin "2") (pinfunction "2_2") (pintype "passive"))
      (node (ref "C43") (pin "2") (pinfunction "2_2") (pintype "passive"))
      (node (ref "C44") (pin "2") (pinfunction "2_2") (pintype "passive"))
      (node (ref "C45") (pin "2") (pinfunction "2_2") (pintype "passive"))
      (node (ref "C46") (pin "2") (pinfunction "2_2") (pintype "passive"))
      (node (ref "C47") (pin "2") (pinfunction "2_2") (pintype "passive"))
      (node (ref "C48") (pin "2") (pinfunction "2_2") (pintype "passive"))
      (node (ref "C49") (pin "2") (pinfunction "2_2") (pintype "passive"))
      (node (ref "C50") (pin "2") (pinfunction "2_2") (pintype "passive"))
      (node (ref "C51") (pin "2") (pinfunction "2_2") (pintype "passive"))
      (node (ref "C52") (pin "2") (pinfunction "2_2") (pintype "passive"))
      (node (ref "C53") (pin "2") (pinfunction "2_2") (pintype "passive"))
      (node (ref "C54") (pin "2") (pinfunction "2_2") (pintype "passive"))
      (node (ref "C55") (pin "2") (pinfunction "2_2") (pintype "passive"))
      (node (ref "C56") (pin "2") (pinfunction "2_2") (pintype "passive"))
      (node (ref "FB5") (pin "2") (pinfunction "2_2") (pintype "passive"))
      (node (ref "R23") (pin "2") (pinfunction "2_2") (pintype "passive"))
      (node (ref "R26") (pin "2") (pinfunction "2_2") (pintype "passive"))
      (node (ref "U2") (pin "A13") (pinfunction "VCCO_MIO1_501_A13") (pintype "passive"))
      (node (ref "U2") (pin "B16") (pinfunction "VCCO_MIO1_501_B16") (pintype "passive"))
      (node (ref "U2") (pin "D12") (pinfunction "VCCO_MIO1_501_D12") (pintype "passive"))
      (node (ref "U2") (pin "E15") (pinfunction "VCCO_MIO1_501_E15") (pintype "passive"))
      (node (ref "U2") (pin "F11") (pinfunction "VCCBATT_0_F11") (pintype "passive"))
      (node (ref "U2") (pin "F8") (pinfunction "VCCPAUX_F8") (pintype "passive"))
      (node (ref "U2") (pin "G9") (pinfunction "VCCPAUX_G9") (pintype "passive"))
      (node (ref "U2") (pin "H8") (pinfunction "VCCPAUX_H8") (pintype "passive"))
      (node (ref "U2") (pin "J11") (pinfunction "VCCAUX_J11") (pintype "passive"))
      (node (ref "U2") (pin "J9") (pinfunction "VCCADC_0_J9") (pintype "passive"))
      (node (ref "U2") (pin "K8") (pinfunction "VCCPAUX_K8") (pintype "passive"))
      (node (ref "U2") (pin "L11") (pinfunction "VCCAUX_L11") (pintype "passive"))
      (node (ref "U2") (pin "M8") (pinfunction "VCCPAUX_M8") (pintype "passive"))
      (node (ref "U2") (pin "N11") (pinfunction "VCCAUX_N11") (pintype "passive"))
      (node (ref "U2") (pin "N9") (pinfunction "VCCAUX_N9") (pintype "passive"))
      (node (ref "U2") (pin "P10") (pinfunction "VCCAUX_P10") (pintype "passive"))
      (node (ref "U2") (pin "R9") (pinfunction "VCCAUX_R9") (pintype "passive"))
    )
    (net (code "38") (name "VCC_3V3") (class "Default")
      (node (ref "C30") (pin "2") (pinfunction "2_2") (pintype "passive"))
      (node (ref "C31") (pin "2") (pinfunction "2_2") (pintype "passive"))
      (node (ref "C57") (pin "2") (pinfunction "2_2") (pintype "passive"))
      (node (ref "C58") (pin "2") (pinfunction "2_2") (pintype "passive"))
      (node (ref "C59") (pin "2") (pinfunction "2_2") (pintype "passive"))
      (node (ref "C60") (pin "2") (pinfunction "2_2") (pintype "passive"))
      (node (ref "C61") (pin "2") (pinfunction "2_2") (pintype "passive"))
      (node (ref "C62") (pin "2") (pinfunction "2_2") (pintype "passive"))
      (node (ref "C63") (pin "2") (pinfunction "2_2") (pintype "passive"))
      (node (ref "C64") (pin "2") (pinfunction "2_2") (pintype "passive"))
      (node (ref "C65") (pin "2") (pinfunction "2_2") (pintype "passive"))
      (node (ref "C66") (pin "2") (pinfunction "2_2") (pintype "passive"))
      (node (ref "C67") (pin "2") (pinfunction "2_2") (pintype "passive"))
      (node (ref "C68") (pin "2") (pinfunction "2_2") (pintype "passive"))
      (node (ref "C69") (pin "2") (pinfunction "2_2") (pintype "passive"))
      (node (ref "C70") (pin "2") (pinfunction "2_2") (pintype "passive"))
      (node (ref "C71") (pin "2") (pinfunction "2_2") (pintype "passive"))
      (node (ref "C72") (pin "2") (pinfunction "2_2") (pintype "passive"))
      (node (ref "C73") (pin "2") (pinfunction "2_2") (pintype "passive"))
      (node (ref "C74") (pin "2") (pinfunction "2_2") (pintype "passive"))
      (node (ref "C75") (pin "2") (pinfunction "2_2") (pintype "passive"))
      (node (ref "C76") (pin "2") (pinfunction "2_2") (pintype "passive"))
      (node (ref "C77") (pin "2") (pinfunction "2_2") (pintype "passive"))
      (node (ref "C88") (pin "2") (pinfunction "2_2") (pintype "passive"))
      (node (ref "R21") (pin "1") (pinfunction "1_1") (pintype "passive"))
      (node (ref "R22") (pin "1") (pinfunction "1_1") (pintype "passive"))
      (node (ref "R27") (pin "2") (pinfunction "2_2") (pintype "passive"))
      (node (ref "R29") (pin "1") (pinfunction "1_1") (pintype "passive"))
      (node (ref "R30") (pin "2") (pinfunction "2_2") (pintype "passive"))
      (node (ref "U2") (pin "B6") (pinfunction "VCCO_MIO0_500_B6") (pintype "passive"))
      (node (ref "U2") (pin "C19") (pinfunction "VCCO_35_C19") (pintype "passive"))
      (node (ref "U2") (pin "D7") (pinfunction "VCCO_MIO0_500_D7") (pintype "passive"))
      (node (ref "U2") (pin "F18") (pinfunction "VCCO_35_F18") (pintype "passive"))
      (node (ref "U2") (pin "H14") (pinfunction "VCCO_35_H14") (pintype "passive"))
      (node (ref "U2") (pin "J17") (pinfunction "VCCO_35_J17") (pintype "passive"))
      (node (ref "U2") (pin "K20") (pinfunction "VCCO_35_K20") (pintype "passive"))
      (node (ref "U2") (pin "K6") (pinfunction "VCCO_0_K6") (pintype "passive"))
      (node (ref "U2") (pin "M16") (pinfunction "VCCO_35_M16") (pintype "passive"))
      (node (ref "U2") (pin "M6") (pinfunction "CFGBVS_0_M6") (pintype "passive"))
      (node (ref "U2") (pin "N19") (pinfunction "VCCO_34_N19") (pintype "passive"))
      (node (ref "U2") (pin "N6") (pinfunction "RSVDVCC3_N6") (pintype "passive"))
      (node (ref "U2") (pin "R15") (pinfunction "VCCO_34_R15") (pintype "passive"))
      (node (ref "U2") (pin "R6") (pinfunction "RSVDVCC2_R6") (pintype "passive"))
      (node (ref "U2") (pin "T18") (pinfunction "VCCO_34_T18") (pintype "passive"))
      (node (ref "U2") (pin "T6") (pinfunction "RSVDVCC1_T6") (pintype "passive"))
      (node (ref "U2") (pin "T8") (pinfunction "VCCO_13_T8") (pintype "passive"))
      (node (ref "U2") (pin "U11") (pinfunction "VCCO_13_U11") (pintype "passive"))
      (node (ref "U2") (pin "V14") (pinfunction "VCCO_34_V14") (pintype "passive"))
      (node (ref "U2") (pin "W17") (pinfunction "VCCO_34_W17") (pintype "passive"))
      (node (ref "U2") (pin "W7") (pinfunction "VCCO_13_W7") (pintype "passive"))
      (node (ref "U2") (pin "Y10") (pinfunction "VCCO_13_Y10") (pintype "passive"))
      (node (ref "U2") (pin "Y20") (pinfunction "VCCO_34_Y20") (pintype "passive"))
      (node (ref "U3") (pin "4") (pinfunction "VCC_4") (pintype "passive"))
      (node (ref "U4") (pin "8") (pinfunction "VCC_8") (pintype "passive"))
      (node (ref "X2") (pin "1") (pinfunction "EN_1") (pintype "passive"))
      (node (ref "X2") (pin "4") (pinfunction "VDD_4") (pintype "passive"))
      (node (ref "X3") (pin "1") (pinfunction "EN_1") (pintype "passive"))
      (node (ref "X3") (pin "4") (pinfunction "VDD_4") (pintype "passive"))
    )
    (net (code "39") (name "unconnected-(U2A-IO_0_34-PadR19)") (class "Default")
      (node (ref "U2") (pin "R19") (pinfunction "IO_0_34_R19") (pintype "passive"))
    )
    (net (code "40") (name "unconnected-(U2A-IO_0_35-PadG14)") (class "Default")
      (node (ref "U2") (pin "G14") (pinfunction "IO_0_35_G14") (pintype "passive"))
    )
    (net (code "41") (name "unconnected-(U2A-IO_25_34-PadT19)") (class "Default")
      (node (ref "U2") (pin "T19") (pinfunction "IO_25_34_T19") (pintype "passive"))
    )
    (net (code "42") (name "unconnected-(U2A-IO_25_35-PadJ15)") (class "Default")
      (node (ref "U2") (pin "J15") (pinfunction "IO_25_35_J15") (pintype "passive"))
    )
    (net (code "43") (name "unconnected-(U2A-IO_L1N_T0_34-PadT10)") (class "Default")
      (node (ref "U2") (pin "T10") (pinfunction "IO_L1N_T0_34_T10") (pintype "passive"))
    )
    (net (code "44") (name "unconnected-(U2A-IO_L1N_T0_AD0N_35-PadB20)") (class "Default")
      (node (ref "U2") (pin "B20") (pinfunction "IO_L1N_T0_AD0N_35_B20") (pintype "passive"))
    )
    (net (code "45") (name "unconnected-(U2A-IO_L1P_T0_34-PadT11)") (class "Default")
      (node (ref "U2") (pin "T11") (pinfunction "IO_L1P_T0_34_T11") (pintype "passive"))
    )
    (net (code "46") (name "unconnected-(U2A-IO_L1P_T0_AD0P_35-PadC20)") (class "Default")
      (node (ref "U2") (pin "C20") (pinfunction "IO_L1P_T0_AD0P_35_C20") (pintype "passive"))
    )
    (net (code "47") (name "unconnected-(U2A-IO_L2N_T0_34-PadU12)") (class "Default")
      (node (ref "U2") (pin "U12") (pinfunction "IO_L2N_T0_34_U12") (pintype "passive"))
    )
    (net (code "48") (name "unconnected-(U2A-IO_L2N_T0_AD8N_35-PadA20)") (class "Default")
      (node (ref "U2") (pin "A20") (pinfunction "IO_L2N_T0_AD8N_35_A20") (pintype "passive"))
    )
    (net (code "49") (name "unconnected-(U2A-IO_L2P_T0_34-PadT12)") (class "Default")
      (node (ref "U2") (pin "T12") (pinfunction "IO_L2P_T0_34_T12") (pintype "passive"))
    )
    (net (code "50") (name "unconnected-(U2A-IO_L2P_T0_AD8P_35-PadB19)") (class "Default")
      (node (ref "U2") (pin "B19") (pinfunction "IO_L2P_T0_AD8P_35_B19") (pintype "passive"))
    )
    (net (code "51") (name "unconnected-(U2A-IO_L3N_T0_DQS_34-PadV13)") (class "Default")
      (node (ref "U2") (pin "V13") (pinfunction "IO_L3N_T0_DQS_34_V13") (pintype "passive"))
    )
    (net (code "52") (name "unconnected-(U2A-IO_L3N_T0_DQS_AD1N_35-PadD18)") (class "Default")
      (node (ref "U2") (pin "D18") (pinfunction "IO_L3N_T0_DQS_AD1N_35_D18") (pintype "passive"))
    )
    (net (code "53") (name "unconnected-(U2A-IO_L3P_T0_DQS_AD1P_35-PadE17)") (class "Default")
      (node (ref "U2") (pin "E17") (pinfunction "IO_L3P_T0_DQS_AD1P_35_E17") (pintype "passive"))
    )
    (net (code "54") (name "unconnected-(U2A-IO_L3P_T0_DQS_PUDC_B_34-PadU13)") (class "Default")
      (node (ref "U2") (pin "U13") (pinfunction "IO_L3P_T0_DQS_PUDC_B_34_U13") (pintype "passive"))
    )
    (net (code "55") (name "unconnected-(U2A-IO_L4N_T0_34-PadW13)") (class "Default")
      (node (ref "U2") (pin "W13") (pinfunction "IO_L4N_T0_34_W13") (pintype "passive"))
    )
    (net (code "56") (name "unconnected-(U2A-IO_L4N_T0_35-PadD20)") (class "Default")
      (node (ref "U2") (pin "D20") (pinfunction "IO_L4N_T0_35_D20") (pintype "passive"))
    )
    (net (code "57") (name "unconnected-(U2A-IO_L4P_T0_34-PadV12)") (class "Default")
      (node (ref "U2") (pin "V12") (pinfunction "IO_L4P_T0_34_V12") (pintype "passive"))
    )
    (net (code "58") (name "unconnected-(U2A-IO_L4P_T0_35-PadD19)") (class "Default")
      (node (ref "U2") (pin "D19") (pinfunction "IO_L4P_T0_35_D19") (pintype "passive"))
    )
    (net (code "59") (name "unconnected-(U2A-IO_L5N_T0_34-PadT15)") (class "Default")
      (node (ref "U2") (pin "T15") (pinfunction "IO_L5N_T0_34_T15") (pintype "passive"))
    )
    (net (code "60") (name "unconnected-(U2A-IO_L5N_T0_AD9N_35-PadE19)") (class "Default")
      (node (ref "U2") (pin "E19") (pinfunction "IO_L5N_T0_AD9N_35_E19") (pintype "passive"))
    )
    (net (code "61") (name "unconnected-(U2A-IO_L5P_T0_34-PadT14)") (class "Default")
      (node (ref "U2") (pin "T14") (pinfunction "IO_L5P_T0_34_T14") (pintype "passive"))
    )
    (net (code "62") (name "unconnected-(U2A-IO_L5P_T0_AD9P_35-PadE18)") (class "Default")
      (node (ref "U2") (pin "E18") (pinfunction "IO_L5P_T0_AD9P_35_E18") (pintype "passive"))
    )
    (net (code "63") (name "unconnected-(U2A-IO_L6N_T0_VREF_34-PadR14)") (class "Default")
      (node (ref "U2") (pin "R14") (pinfunction "IO_L6N_T0_VREF_34_R14") (pintype "passive"))
    )
    (net (code "64") (name "unconnected-(U2A-IO_L6N_T0_VREF_35-PadF17)") (class "Default")
      (node (ref "U2") (pin "F17") (pinfunction "IO_L6N_T0_VREF_35_F17") (pintype "passive"))
    )
    (net (code "65") (name "unconnected-(U2A-IO_L6P_T0_34-PadP14)") (class "Default")
      (node (ref "U2") (pin "P14") (pinfunction "IO_L6P_T0_34_P14") (pintype "passive"))
    )
    (net (code "66") (name "unconnected-(U2A-IO_L6P_T0_35-PadF16)") (class "Default")
      (node (ref "U2") (pin "F16") (pinfunction "IO_L6P_T0_35_F16") (pintype "passive"))
    )
    (net (code "67") (name "unconnected-(U2A-IO_L7N_T1_34-PadY17)") (class "Default")
      (node (ref "U2") (pin "Y17") (pinfunction "IO_L7N_T1_34_Y17") (pintype "passive"))
    )
    (net (code "68") (name "unconnected-(U2A-IO_L7N_T1_AD2N_35-PadM20)") (class "Default")
      (node (ref "U2") (pin "M20") (pinfunction "IO_L7N_T1_AD2N_35_M20") (pintype "passive"))
    )
    (net (code "69") (name "unconnected-(U2A-IO_L7P_T1_34-PadY16)") (class "Default")
      (node (ref "U2") (pin "Y16") (pinfunction "IO_L7P_T1_34_Y16") (pintype "passive"))
    )
    (net (code "70") (name "unconnected-(U2A-IO_L7P_T1_AD2P_35-PadM19)") (class "Default")
      (node (ref "U2") (pin "M19") (pinfunction "IO_L7P_T1_AD2P_35_M19") (pintype "passive"))
    )
    (net (code "71") (name "unconnected-(U2A-IO_L8N_T1_34-PadY14)") (class "Default")
      (node (ref "U2") (pin "Y14") (pinfunction "IO_L8N_T1_34_Y14") (pintype "passive"))
    )
    (net (code "72") (name "unconnected-(U2A-IO_L8N_T1_AD10N_35-PadM18)") (class "Default")
      (node (ref "U2") (pin "M18") (pinfunction "IO_L8N_T1_AD10N_35_M18") (pintype "passive"))
    )
    (net (code "73") (name "unconnected-(U2A-IO_L8P_T1_34-PadW14)") (class "Default")
      (node (ref "U2") (pin "W14") (pinfunction "IO_L8P_T1_34_W14") (pintype "passive"))
    )
    (net (code "74") (name "unconnected-(U2A-IO_L8P_T1_AD10P_35-PadM17)") (class "Default")
      (node (ref "U2") (pin "M17") (pinfunction "IO_L8P_T1_AD10P_35_M17") (pintype "passive"))
    )
    (net (code "75") (name "unconnected-(U2A-IO_L9N_T1_DQS_34-PadU17)") (class "Default")
      (node (ref "U2") (pin "U17") (pinfunction "IO_L9N_T1_DQS_34_U17") (pintype "passive"))
    )
    (net (code "76") (name "unconnected-(U2A-IO_L9N_T1_DQS_AD3N_35-PadL20)") (class "Default")
      (node (ref "U2") (pin "L20") (pinfunction "IO_L9N_T1_DQS_AD3N_35_L20") (pintype "passive"))
    )
    (net (code "77") (name "unconnected-(U2A-IO_L9P_T1_DQS_34-PadT16)") (class "Default")
      (node (ref "U2") (pin "T16") (pinfunction "IO_L9P_T1_DQS_34_T16") (pintype "passive"))
    )
    (net (code "78") (name "unconnected-(U2A-IO_L9P_T1_DQS_AD3P_35-PadL19)") (class "Default")
      (node (ref "U2") (pin "L19") (pinfunction "IO_L9P_T1_DQS_AD3P_35_L19") (pintype "passive"))
    )
    (net (code "79") (name "unconnected-(U2A-IO_L10N_T1_34-PadW15)") (class "Default")
      (node (ref "U2") (pin "W15") (pinfunction "IO_L10N_T1_34_W15") (pintype "passive"))
    )
    (net (code "80") (name "unconnected-(U2A-IO_L10N_T1_AD11N_35-PadJ19)") (class "Default")
      (node (ref "U2") (pin "J19") (pinfunction "IO_L10N_T1_AD11N_35_J19") (pintype "passive"))
    )
    (net (code "81") (name "unconnected-(U2A-IO_L10P_T1_34-PadV15)") (class "Default")
      (node (ref "U2") (pin "V15") (pinfunction "IO_L10P_T1_34_V15") (pintype "passive"))
    )
    (net (code "82") (name "unconnected-(U2A-IO_L10P_T1_AD11P_35-PadK19)") (class "Default")
      (node (ref "U2") (pin "K19") (pinfunction "IO_L10P_T1_AD11P_35_K19") (pintype "passive"))
    )
    (net (code "83") (name "unconnected-(U2A-IO_L11N_T1_SRCC_34-PadU15)") (class "Default")
      (node (ref "U2") (pin "U15") (pinfunction "IO_L11N_T1_SRCC_34_U15") (pintype "passive"))
    )
    (net (code "84") (name "unconnected-(U2A-IO_L11N_T1_SRCC_35-PadL17)") (class "Default")
      (node (ref "U2") (pin "L17") (pinfunction "IO_L11N_T1_SRCC_35_L17") (pintype "passive"))
    )
    (net (code "85") (name "unconnected-(U2A-IO_L11P_T1_SRCC_34-PadU14)") (class "Default")
      (node (ref "U2") (pin "U14") (pinfunction "IO_L11P_T1_SRCC_34_U14") (pintype "passive"))
    )
    (net (code "86") (name "unconnected-(U2A-IO_L11P_T1_SRCC_35-PadL16)") (class "Default")
      (node (ref "U2") (pin "L16") (pinfunction "IO_L11P_T1_SRCC_35_L16") (pintype "passive"))
    )
    (net (code "87") (name "unconnected-(U2A-IO_L12N_T1_MRCC_34-PadU19)") (class "Default")
      (node (ref "U2") (pin "U19") (pinfunction "IO_L12N_T1_MRCC_34_U19") (pintype "passive"))
    )
    (net (code "88") (name "unconnected-(U2A-IO_L12N_T1_MRCC_35-PadK18)") (class "Default")
      (node (ref "U2") (pin "K18") (pinfunction "IO_L12N_T1_MRCC_35_K18") (pintype "passive"))
    )
    (net (code "89") (name "unconnected-(U2A-IO_L12P_T1_MRCC_34-PadU18)") (class "Default")
      (node (ref "U2") (pin "U18") (pinfunction "IO_L12P_T1_MRCC_34_U18") (pintype "passive"))
    )
    (net (code "90") (name "unconnected-(U2A-IO_L12P_T1_MRCC_35-PadK17)") (class "Default")
      (node (ref "U2") (pin "K17") (pinfunction "IO_L12P_T1_MRCC_35_K17") (pintype "passive"))
    )
    (net (code "91") (name "unconnected-(U2A-IO_L13N_T2_MRCC_35-PadH17)") (class "Default")
      (node (ref "U2") (pin "H17") (pinfunction "IO_L13N_T2_MRCC_35_H17") (pintype "passive"))
    )
    (net (code "92") (name "unconnected-(U2A-IO_L13P_T2_MRCC_34-PadN18)") (class "Default")
      (node (ref "U2") (pin "N18") (pinfunction "IO_L13P_T2_MRCC_34_N18") (pintype "passive"))
    )
    (net (code "93") (name "unconnected-(U2A-IO_L13P_T2_MRCC_35-PadH16)") (class "Default")
      (node (ref "U2") (pin "H16") (pinfunction "IO_L13P_T2_MRCC_35_H16") (pintype "passive"))
    )
    (net (code "94") (name "unconnected-(U2A-IO_L14N_T2_AD4N_SRCC_35-PadH18)") (class "Default")
      (node (ref "U2") (pin "H18") (pinfunction "IO_L14N_T2_AD4N_SRCC_35_H18") (pintype "passive"))
    )
    (net (code "95") (name "unconnected-(U2A-IO_L14N_T2_SRCC_34-PadP20)") (class "Default")
      (node (ref "U2") (pin "P20") (pinfunction "IO_L14N_T2_SRCC_34_P20") (pintype "passive"))
    )
    (net (code "96") (name "unconnected-(U2A-IO_L14P_T2_AD4P_SRCC_35-PadJ18)") (class "Default")
      (node (ref "U2") (pin "J18") (pinfunction "IO_L14P_T2_AD4P_SRCC_35_J18") (pintype "passive"))
    )
    (net (code "97") (name "unconnected-(U2A-IO_L14P_T2_SRCC_34-PadN20)") (class "Default")
      (node (ref "U2") (pin "N20") (pinfunction "IO_L14P_T2_SRCC_34_N20") (pintype "passive"))
    )
    (net (code "98") (name "unconnected-(U2A-IO_L15N_T2_DQS_34-PadU20)") (class "Default")
      (node (ref "U2") (pin "U20") (pinfunction "IO_L15N_T2_DQS_34_U20") (pintype "passive"))
    )
    (net (code "99") (name "unconnected-(U2A-IO_L15N_T2_DQS_AD12N_35-PadF20)") (class "Default")
      (node (ref "U2") (pin "F20") (pinfunction "IO_L15N_T2_DQS_AD12N_35_F20") (pintype "passive"))
    )
    (net (code "100") (name "unconnected-(U2A-IO_L15P_T2_DQS_34-PadT20)") (class "Default")
      (node (ref "U2") (pin "T20") (pinfunction "IO_L15P_T2_DQS_34_T20") (pintype "passive"))
    )
    (net (code "101") (name "unconnected-(U2A-IO_L15P_T2_DQS_AD12P_35-PadF19)") (class "Default")
      (node (ref "U2") (pin "F19") (pinfunction "IO_L15P_T2_DQS_AD12P_35_F19") (pintype "passive"))
    )
    (net (code "102") (name "unconnected-(U2A-IO_L16N_T2_34-PadW20)") (class "Default")
      (node (ref "U2") (pin "W20") (pinfunction "IO_L16N_T2_34_W20") (pintype "passive"))
    )
    (net (code "103") (name "unconnected-(U2A-IO_L16N_T2_35-PadG18)") (class "Default")
      (node (ref "U2") (pin "G18") (pinfunction "IO_L16N_T2_35_G18") (pintype "passive"))
    )
    (net (code "104") (name "unconnected-(U2A-IO_L16P_T2_34-PadV20)") (class "Default")
      (node (ref "U2") (pin "V20") (pinfunction "IO_L16P_T2_34_V20") (pintype "passive"))
    )
    (net (code "105") (name "unconnected-(U2A-IO_L16P_T2_35-PadG17)") (class "Default")
      (node (ref "U2") (pin "G17") (pinfunction "IO_L16P_T2_35_G17") (pintype "passive"))
    )
    (net (code "106") (name "unconnected-(U2A-IO_L17N_T2_34-PadY19)") (class "Default")
      (node (ref "U2") (pin "Y19") (pinfunction "IO_L17N_T2_34_Y19") (pintype "passive"))
    )
    (net (code "107") (name "unconnected-(U2A-IO_L17N_T2_AD5N_35-PadH20)") (class "Default")
      (node (ref "U2") (pin "H20") (pinfunction "IO_L17N_T2_AD5N_35_H20") (pintype "passive"))
    )
    (net (code "108") (name "unconnected-(U2A-IO_L17P_T2_34-PadY18)") (class "Default")
      (node (ref "U2") (pin "Y18") (pinfunction "IO_L17P_T2_34_Y18") (pintype "passive"))
    )
    (net (code "109") (name "unconnected-(U2A-IO_L17P_T2_AD5P_35-PadJ20)") (class "Default")
      (node (ref "U2") (pin "J20") (pinfunction "IO_L17P_T2_AD5P_35_J20") (pintype "passive"))
    )
    (net (code "110") (name "unconnected-(U2A-IO_L18N_T2_34-PadW16)") (class "Default")
      (node (ref "U2") (pin "W16") (pinfunction "IO_L18N_T2_34_W16") (pintype "passive"))
    )
    (net (code "111") (name "unconnected-(U2A-IO_L18N_T2_AD13N_35-PadG20)") (class "Default")
      (node (ref "U2") (pin "G20") (pinfunction "IO_L18N_T2_AD13N_35_G20") (pintype "passive"))
    )
    (net (code "112") (name "unconnected-(U2A-IO_L18P_T2_34-PadV16)") (class "Default")
      (node (ref "U2") (pin "V16") (pinfunction "IO_L18P_T2_34_V16") (pintype "passive"))
    )
    (net (code "113") (name "unconnected-(U2A-IO_L18P_T2_AD13P_35-PadG19)") (class "Default")
      (node (ref "U2") (pin "G19") (pinfunction "IO_L18P_T2_AD13P_35_G19") (pintype "passive"))
    )
    (net (code "114") (name "unconnected-(U2A-IO_L19N_T3_VREF_34-PadR17)") (class "Default")
      (node (ref "U2") (pin "R17") (pinfunction "IO_L19N_T3_VREF_34_R17") (pintype "passive"))
    )
    (net (code "115") (name "unconnected-(U2A-IO_L19N_T3_VREF_35-PadG15)") (class "Default")
      (node (ref "U2") (pin "G15") (pinfunction "IO_L19N_T3_VREF_35_G15") (pintype "passive"))
    )
    (net (code "116") (name "unconnected-(U2A-IO_L19P_T3_34-PadR16)") (class "Default")
      (node (ref "U2") (pin "R16") (pinfunction "IO_L19P_T3_34_R16") (pintype "passive"))
    )
    (net (code "117") (name "unconnected-(U2A-IO_L19P_T3_35-PadH15)") (class "Default")
      (node (ref "U2") (pin "H15") (pinfunction "IO_L19P_T3_35_H15") (pintype "passive"))
    )
    (net (code "118") (name "unconnected-(U2A-IO_L20N_T3_34-PadR18)") (class "Default")
      (node (ref "U2") (pin "R18") (pinfunction "IO_L20N_T3_34_R18") (pintype "passive"))
    )
    (net (code "119") (name "unconnected-(U2A-IO_L20N_T3_AD6N_35-PadJ14)") (class "Default")
      (node (ref "U2") (pin "J14") (pinfunction "IO_L20N_T3_AD6N_35_J14") (pintype "passive"))
    )
    (net (code "120") (name "unconnected-(U2A-IO_L20P_T3_34-PadT17)") (class "Default")
      (node (ref "U2") (pin "T17") (pinfunction "IO_L20P_T3_34_T17") (pintype "passive"))
    )
    (net (code "121") (name "unconnected-(U2A-IO_L20P_T3_AD6P_35-PadK14)") (class "Default")
      (node (ref "U2") (pin "K14") (pinfunction "IO_L20P_T3_AD6P_35_K14") (pintype "passive"))
    )
    (net (code "122") (name "unconnected-(U2A-IO_L21N_T3_DQS_34-PadV18)") (class "Default")
      (node (ref "U2") (pin "V18") (pinfunction "IO_L21N_T3_DQS_34_V18") (pintype "passive"))
    )
    (net (code "123") (name "unconnected-(U2A-IO_L21N_T3_DQS_AD14N_35-PadN16)") (class "Default")
      (node (ref "U2") (pin "N16") (pinfunction "IO_L21N_T3_DQS_AD14N_35_N16") (pintype "passive"))
    )
    (net (code "124") (name "unconnected-(U2A-IO_L21P_T3_DQS_34-PadV17)") (class "Default")
      (node (ref "U2") (pin "V17") (pinfunction "IO_L21P_T3_DQS_34_V17") (pintype "passive"))
    )
    (net (code "125") (name "unconnected-(U2A-IO_L21P_T3_DQS_AD14P_35-PadN15)") (class "Default")
      (node (ref "U2") (pin "N15") (pinfunction "IO_L21P_T3_DQS_AD14P_35_N15") (pintype "passive"))
    )
    (net (code "126") (name "unconnected-(U2A-IO_L22N_T3_34-PadW19)") (class "Default")
      (node (ref "U2") (pin "W19") (pinfunction "IO_L22N_T3_34_W19") (pintype "passive"))
    )
    (net (code "127") (name "unconnected-(U2A-IO_L22N_T3_AD7N_35-PadL15)") (class "Default")
      (node (ref "U2") (pin "L15") (pinfunction "IO_L22N_T3_AD7N_35_L15") (pintype "passive"))
    )
    (net (code "128") (name "unconnected-(U2A-IO_L22P_T3_34-PadW18)") (class "Default")
      (node (ref "U2") (pin "W18") (pinfunction "IO_L22P_T3_34_W18") (pintype "passive"))
    )
    (net (code "129") (name "unconnected-(U2A-IO_L22P_T3_AD7P_35-PadL14)") (class "Default")
      (node (ref "U2") (pin "L14") (pinfunction "IO_L22P_T3_AD7P_35_L14") (pintype "passive"))
    )
    (net (code "130") (name "unconnected-(U2A-IO_L23N_T3_34-PadP18)") (class "Default")
      (node (ref "U2") (pin "P18") (pinfunction "IO_L23N_T3_34_P18") (pintype "passive"))
    )
    (net (code "131") (name "unconnected-(U2A-IO_L23N_T3_35-PadM15)") (class "Default")
      (node (ref "U2") (pin "M15") (pinfunction "IO_L23N_T3_35_M15") (pintype "passive"))
    )
    (net (code "132") (name "unconnected-(U2A-IO_L23P_T3_34-PadN17)") (class "Default")
      (node (ref "U2") (pin "N17") (pinfunction "IO_L23P_T3_34_N17") (pintype "passive"))
    )
    (net (code "133") (name "unconnected-(U2A-IO_L23P_T3_35-PadM14)") (class "Default")
      (node (ref "U2") (pin "M14") (pinfunction "IO_L23P_T3_35_M14") (pintype "passive"))
    )
    (net (code "134") (name "unconnected-(U2A-IO_L24N_T3_34-PadP16)") (class "Default")
      (node (ref "U2") (pin "P16") (pinfunction "IO_L24N_T3_34_P16") (pintype "passive"))
    )
    (net (code "135") (name "unconnected-(U2A-IO_L24N_T3_AD15N_35-PadJ16)") (class "Default")
      (node (ref "U2") (pin "J16") (pinfunction "IO_L24N_T3_AD15N_35_J16") (pintype "passive"))
    )
    (net (code "136") (name "unconnected-(U2A-IO_L24P_T3_34-PadP15)") (class "Default")
      (node (ref "U2") (pin "P15") (pinfunction "IO_L24P_T3_34_P15") (pintype "passive"))
    )
    (net (code "137") (name "unconnected-(U2A-IO_L24P_T3_AD15P_35-PadK16)") (class "Default")
      (node (ref "U2") (pin "K16") (pinfunction "IO_L24P_T3_AD15P_35_K16") (pintype "passive"))
    )
    (net (code "138") (name "unconnected-(U2B-IO_L6N_T0_VREF_13-PadV5)") (class "Default")
      (node (ref "U2") (pin "V5") (pinfunction "IO_L6N_T0_VREF_13_V5") (pintype "passive"))
    )
    (net (code "139") (name "unconnected-(U2B-IO_L11N_T1_SRCC_13-PadV7)") (class "Default")
      (node (ref "U2") (pin "V7") (pinfunction "IO_L11N_T1_SRCC_13_V7") (pintype "passive"))
    )
    (net (code "140") (name "unconnected-(U2B-IO_L11P_T1_SRCC_13-PadU7)") (class "Default")
      (node (ref "U2") (pin "U7") (pinfunction "IO_L11P_T1_SRCC_13_U7") (pintype "passive"))
    )
    (net (code "141") (name "unconnected-(U2B-IO_L12N_T1_MRCC_13-PadU10)") (class "Default")
      (node (ref "U2") (pin "U10") (pinfunction "IO_L12N_T1_MRCC_13_U10") (pintype "passive"))
    )
    (net (code "142") (name "unconnected-(U2B-IO_L12P_T1_MRCC_13-PadT9)") (class "Default")
      (node (ref "U2") (pin "T9") (pinfunction "IO_L12P_T1_MRCC_13_T9") (pintype "passive"))
    )
    (net (code "143") (name "unconnected-(U2B-IO_L13N_T2_MRCC_13-PadY6)") (class "Default")
      (node (ref "U2") (pin "Y6") (pinfunction "IO_L13N_T2_MRCC_13_Y6") (pintype "passive"))
    )
    (net (code "144") (name "unconnected-(U2B-IO_L13P_T2_MRCC_13-PadY7)") (class "Default")
      (node (ref "U2") (pin "Y7") (pinfunction "IO_L13P_T2_MRCC_13_Y7") (pintype "passive"))
    )
    (net (code "145") (name "unconnected-(U2B-IO_L14N_T2_SRCC_13-PadY8)") (class "Default")
      (node (ref "U2") (pin "Y8") (pinfunction "IO_L14N_T2_SRCC_13_Y8") (pintype "passive"))
    )
    (net (code "146") (name "unconnected-(U2B-IO_L14P_T2_SRCC_13-PadY9)") (class "Default")
      (node (ref "U2") (pin "Y9") (pinfunction "IO_L14P_T2_SRCC_13_Y9") (pintype "passive"))
    )
    (net (code "147") (name "unconnected-(U2B-IO_L15N_T2_DQS_13-PadW8)") (class "Default")
      (node (ref "U2") (pin "W8") (pinfunction "IO_L15N_T2_DQS_13_W8") (pintype "passive"))
    )
    (net (code "148") (name "unconnected-(U2B-IO_L15P_T2_DQS_13-PadV8)") (class "Default")
      (node (ref "U2") (pin "V8") (pinfunction "IO_L15P_T2_DQS_13_V8") (pintype "passive"))
    )
    (net (code "149") (name "unconnected-(U2B-IO_L16N_T2_13-PadW9)") (class "Default")
      (node (ref "U2") (pin "W9") (pinfunction "IO_L16N_T2_13_W9") (pintype "passive"))
    )
    (net (code "150") (name "unconnected-(U2B-IO_L16P_T2_13-PadW10)") (class "Default")
      (node (ref "U2") (pin "W10") (pinfunction "IO_L16P_T2_13_W10") (pintype "passive"))
    )
    (net (code "151") (name "unconnected-(U2B-IO_L17N_T2_13-PadU8)") (class "Default")
      (node (ref "U2") (pin "U8") (pinfunction "IO_L17N_T2_13_U8") (pintype "passive"))
    )
    (net (code "152") (name "unconnected-(U2B-IO_L17P_T2_13-PadU9)") (class "Default")
      (node (ref "U2") (pin "U9") (pinfunction "IO_L17P_T2_13_U9") (pintype "passive"))
    )
    (net (code "153") (name "unconnected-(U2B-IO_L18N_T2_13-PadY11)") (class "Default")
      (node (ref "U2") (pin "Y11") (pinfunction "IO_L18N_T2_13_Y11") (pintype "passive"))
    )
    (net (code "154") (name "unconnected-(U2B-IO_L18P_T2_13-PadW11)") (class "Default")
      (node (ref "U2") (pin "W11") (pinfunction "IO_L18P_T2_13_W11") (pintype "passive"))
    )
    (net (code "155") (name "unconnected-(U2B-IO_L19N_T3_VREF_13-PadU5)") (class "Default")
      (node (ref "U2") (pin "U5") (pinfunction "IO_L19N_T3_VREF_13_U5") (pintype "passive"))
    )
    (net (code "156") (name "unconnected-(U2B-IO_L19P_T3_13-PadT5)") (class "Default")
      (node (ref "U2") (pin "T5") (pinfunction "IO_L19P_T3_13_T5") (pintype "passive"))
    )
    (net (code "157") (name "unconnected-(U2B-IO_L20N_T3_13-PadY13)") (class "Default")
      (node (ref "U2") (pin "Y13") (pinfunction "IO_L20N_T3_13_Y13") (pintype "passive"))
    )
    (net (code "158") (name "unconnected-(U2B-IO_L20P_T3_13-PadY12)") (class "Default")
      (node (ref "U2") (pin "Y12") (pinfunction "IO_L20P_T3_13_Y12") (pintype "passive"))
    )
    (net (code "159") (name "unconnected-(U2B-IO_L21N_T3_DQS_13-PadV10)") (class "Default")
      (node (ref "U2") (pin "V10") (pinfunction "IO_L21N_T3_DQS_13_V10") (pintype "passive"))
    )
    (net (code "160") (name "unconnected-(U2B-IO_L21P_T3_DQS_13-PadV11)") (class "Default")
      (node (ref "U2") (pin "V11") (pinfunction "IO_L21P_T3_DQS_13_V11") (pintype "passive"))
    )
    (net (code "161") (name "unconnected-(U2B-IO_L22N_T3_13-PadW6)") (class "Default")
      (node (ref "U2") (pin "W6") (pinfunction "IO_L22N_T3_13_W6") (pintype "passive"))
    )
    (net (code "162") (name "unconnected-(U2B-IO_L22P_T3_13-PadV6)") (class "Default")
      (node (ref "U2") (pin "V6") (pinfunction "IO_L22P_T3_13_V6") (pintype "passive"))
    )
    (net (code "163") (name "unconnected-(U2B-PS_MIO0_500-PadE6)") (class "Default")
      (node (ref "U2") (pin "E6") (pinfunction "PS_MIO0_500_E6") (pintype "passive"))
    )
    (net (code "164") (name "unconnected-(U2B-PS_MIO7_500-PadD8)") (class "Default")
      (node (ref "U2") (pin "D8") (pinfunction "PS_MIO7_500_D8") (pintype "passive"))
    )
    (net (code "165") (name "unconnected-(U2B-PS_MIO8_500-PadD5)") (class "Default")
      (node (ref "U2") (pin "D5") (pinfunction "PS_MIO8_500_D5") (pintype "passive"))
    )
    (net (code "166") (name "unconnected-(U2B-PS_MIO9_500-PadB5)") (class "Default")
      (node (ref "U2") (pin "B5") (pinfunction "PS_MIO9_500_B5") (pintype "passive"))
    )
    (net (code "167") (name "unconnected-(U2B-PS_MIO10_500-PadE9)") (class "Default")
      (node (ref "U2") (pin "E9") (pinfunction "PS_MIO10_500_E9") (pintype "passive"))
    )
    (net (code "168") (name "unconnected-(U2B-PS_MIO11_500-PadC6)") (class "Default")
      (node (ref "U2") (pin "C6") (pinfunction "PS_MIO11_500_C6") (pintype "passive"))
    )
    (net (code "169") (name "unconnected-(U2B-PS_MIO16_501-PadA19)") (class "Default")
      (node (ref "U2") (pin "A19") (pinfunction "PS_MIO16_501_A19") (pintype "passive"))
    )
    (net (code "170") (name "unconnected-(U2B-PS_MIO17_501-PadE14)") (class "Default")
      (node (ref "U2") (pin "E14") (pinfunction "PS_MIO17_501_E14") (pintype "passive"))
    )
    (net (code "171") (name "unconnected-(U2B-PS_MIO18_501-PadB18)") (class "Default")
      (node (ref "U2") (pin "B18") (pinfunction "PS_MIO18_501_B18") (pintype "passive"))
    )
    (net (code "172") (name "unconnected-(U2B-PS_MIO19_501-PadD10)") (class "Default")
      (node (ref "U2") (pin "D10") (pinfunction "PS_MIO19_501_D10") (pintype "passive"))
    )
    (net (code "173") (name "unconnected-(U2B-PS_MIO20_501-PadA17)") (class "Default")
      (node (ref "U2") (pin "A17") (pinfunction "PS_MIO20_501_A17") (pintype "passive"))
    )
    (net (code "174") (name "unconnected-(U2B-PS_MIO21_501-PadF14)") (class "Default")
      (node (ref "U2") (pin "F14") (pinfunction "PS_MIO21_501_F14") (pintype "passive"))
    )
    (net (code "175") (name "unconnected-(U2B-PS_MIO22_501-PadB17)") (class "Default")
      (node (ref "U2") (pin "B17") (pinfunction "PS_MIO22_501_B17") (pintype "passive"))
    )
    (net (code "176") (name "unconnected-(U2B-PS_MIO23_501-PadD11)") (class "Default")
      (node (ref "U2") (pin "D11") (pinfunction "PS_MIO23_501_D11") (pintype "passive"))
    )
    (net (code "177") (name "unconnected-(U2B-PS_MIO24_501-PadA16)") (class "Default")
      (node (ref "U2") (pin "A16") (pinfunction "PS_MIO24_501_A16") (pintype "passive"))
    )
    (net (code "178") (name "unconnected-(U2B-PS_MIO25_501-PadF15)") (class "Default")
      (node (ref "U2") (pin "F15") (pinfunction "PS_MIO25_501_F15") (pintype "passive"))
    )
    (net (code "179") (name "unconnected-(U2B-PS_MIO26_501-PadA15)") (class "Default")
      (node (ref "U2") (pin "A15") (pinfunction "PS_MIO26_501_A15") (pintype "passive"))
    )
    (net (code "180") (name "unconnected-(U2B-PS_MIO27_501-PadD13)") (class "Default")
      (node (ref "U2") (pin "D13") (pinfunction "PS_MIO27_501_D13") (pintype "passive"))
    )
    (net (code "181") (name "unconnected-(U2B-PS_MIO28_501-PadC16)") (class "Default")
      (node (ref "U2") (pin "C16") (pinfunction "PS_MIO28_501_C16") (pintype "passive"))
    )
    (net (code "182") (name "unconnected-(U2B-PS_MIO29_501-PadC13)") (class "Default")
      (node (ref "U2") (pin "C13") (pinfunction "PS_MIO29_501_C13") (pintype "passive"))
    )
    (net (code "183") (name "unconnected-(U2B-PS_MIO30_501-PadC15)") (class "Default")
      (node (ref "U2") (pin "C15") (pinfunction "PS_MIO30_501_C15") (pintype "passive"))
    )
    (net (code "184") (name "unconnected-(U2B-PS_MIO31_501-PadE16)") (class "Default")
      (node (ref "U2") (pin "E16") (pinfunction "PS_MIO31_501_E16") (pintype "passive"))
    )
    (net (code "185") (name "unconnected-(U2B-PS_MIO32_501-PadA14)") (class "Default")
      (node (ref "U2") (pin "A14") (pinfunction "PS_MIO32_501_A14") (pintype "passive"))
    )
    (net (code "186") (name "unconnected-(U2B-PS_MIO33_501-PadD15)") (class "Default")
      (node (ref "U2") (pin "D15") (pinfunction "PS_MIO33_501_D15") (pintype "passive"))
    )
    (net (code "187") (name "unconnected-(U2B-PS_MIO34_501-PadA12)") (class "Default")
      (node (ref "U2") (pin "A12") (pinfunction "PS_MIO34_501_A12") (pintype "passive"))
    )
    (net (code "188") (name "unconnected-(U2B-PS_MIO35_501-PadF12)") (class "Default")
      (node (ref "U2") (pin "F12") (pinfunction "PS_MIO35_501_F12") (pintype "passive"))
    )
    (net (code "189") (name "unconnected-(U2B-PS_MIO36_501-PadA11)") (class "Default")
      (node (ref "U2") (pin "A11") (pinfunction "PS_MIO36_501_A11") (pintype "passive"))
    )
    (net (code "190") (name "unconnected-(U2B-PS_MIO37_501-PadA10)") (class "Default")
      (node (ref "U2") (pin "A10") (pinfunction "PS_MIO37_501_A10") (pintype "passive"))
    )
    (net (code "191") (name "unconnected-(U2B-PS_MIO38_501-PadE13)") (class "Default")
      (node (ref "U2") (pin "E13") (pinfunction "PS_MIO38_501_E13") (pintype "passive"))
    )
    (net (code "192") (name "unconnected-(U2B-PS_MIO39_501-PadC18)") (class "Default")
      (node (ref "U2") (pin "C18") (pinfunction "PS_MIO39_501_C18") (pintype "passive"))
    )
    (net (code "193") (name "unconnected-(U2B-PS_MIO40_501-PadD14)") (class "Default")
      (node (ref "U2") (pin "D14") (pinfunction "PS_MIO40_501_D14") (pintype "passive"))
    )
    (net (code "194") (name "unconnected-(U2B-PS_MIO41_501-PadC17)") (class "Default")
      (node (ref "U2") (pin "C17") (pinfunction "PS_MIO41_501_C17") (pintype "passive"))
    )
    (net (code "195") (name "unconnected-(U2B-PS_MIO42_501-PadE12)") (class "Default")
      (node (ref "U2") (pin "E12") (pinfunction "PS_MIO42_501_E12") (pintype "passive"))
    )
    (net (code "196") (name "unconnected-(U2B-PS_MIO43_501-PadA9)") (class "Default")
      (node (ref "U2") (pin "A9") (pinfunction "PS_MIO43_501_A9") (pintype "passive"))
    )
    (net (code "197") (name "unconnected-(U2B-PS_MIO44_501-PadF13)") (class "Default")
      (node (ref "U2") (pin "F13") (pinfunction "PS_MIO44_501_F13") (pintype "passive"))
    )
    (net (code "198") (name "unconnected-(U2B-PS_MIO45_501-PadB15)") (class "Default")
      (node (ref "U2") (pin "B15") (pinfunction "PS_MIO45_501_B15") (pintype "passive"))
    )
    (net (code "199") (name "unconnected-(U2B-PS_MIO46_501-PadD16)") (class "Default")
      (node (ref "U2") (pin "D16") (pinfunction "PS_MIO46_501_D16") (pintype "passive"))
    )
    (net (code "200") (name "unconnected-(U2B-PS_MIO47_501-PadB14)") (class "Default")
      (node (ref "U2") (pin "B14") (pinfunction "PS_MIO47_501_B14") (pintype "passive"))
    )
    (net (code "201") (name "unconnected-(U2B-PS_MIO48_501-PadB12)") (class "Default")
      (node (ref "U2") (pin "B12") (pinfunction "PS_MIO48_501_B12") (pintype "passive"))
    )
    (net (code "202") (name "unconnected-(U2B-PS_MIO49_501-PadC12)") (class "Default")
      (node (ref "U2") (pin "C12") (pinfunction "PS_MIO49_501_C12") (pintype "passive"))
    )
    (net (code "203") (name "unconnected-(U2B-PS_MIO50_501-PadB13)") (class "Default")
      (node (ref "U2") (pin "B13") (pinfunction "PS_MIO50_501_B13") (pintype "passive"))
    )
    (net (code "204") (name "unconnected-(U2B-PS_MIO51_501-PadB9)") (class "Default")
      (node (ref "U2") (pin "B9") (pinfunction "PS_MIO51_501_B9") (pintype "passive"))
    )
    (net (code "205") (name "unconnected-(U2B-PS_MIO52_501-PadC10)") (class "Default")
      (node (ref "U2") (pin "C10") (pinfunction "PS_MIO52_501_C10") (pintype "passive"))
    )
    (net (code "206") (name "unconnected-(U2B-PS_MIO53_501-PadC11)") (class "Default")
      (node (ref "U2") (pin "C11") (pinfunction "PS_MIO53_501_C11") (pintype "passive"))
    )
    (net (code "207") (name "unconnected-(U2B-VN_0-PadL10)") (class "Default")
      (node (ref "U2") (pin "L10") (pinfunction "VN_0_L10") (pintype "passive"))
    )
    (net (code "208") (name "unconnected-(U2B-VP_0-PadK9)") (class "Default")
      (node (ref "U2") (pin "K9") (pinfunction "VP_0_K9") (pintype "passive"))
    )
    (net (code "209") (name "unconnected-(U2C-PS_DDR_A0_502-PadN2)") (class "Default")
      (node (ref "U2") (pin "N2") (pinfunction "PS_DDR_A0_502_N2") (pintype "passive"))
    )
    (net (code "210") (name "unconnected-(U2C-PS_DDR_A1_502-PadK2)") (class "Default")
      (node (ref "U2") (pin "K2") (pinfunction "PS_DDR_A1_502_K2") (pintype "passive"))
    )
    (net (code "211") (name "unconnected-(U2C-PS_DDR_A2_502-PadM3)") (class "Default")
      (node (ref "U2") (pin "M3") (pinfunction "PS_DDR_A2_502_M3") (pintype "passive"))
    )
    (net (code "212") (name "unconnected-(U2C-PS_DDR_A3_502-PadK3)") (class "Default")
      (node (ref "U2") (pin "K3") (pinfunction "PS_DDR_A3_502_K3") (pintype "passive"))
    )
    (net (code "213") (name "unconnected-(U2C-PS_DDR_A4_502-PadM4)") (class "Default")
      (node (ref "U2") (pin "M4") (pinfunction "PS_DDR_A4_502_M4") (pintype "passive"))
    )
    (net (code "214") (name "unconnected-(U2C-PS_DDR_A5_502-PadL1)") (class "Default")
      (node (ref "U2") (pin "L1") (pinfunction "PS_DDR_A5_502_L1") (pintype "passive"))
    )
    (net (code "215") (name "unconnected-(U2C-PS_DDR_A6_502-PadL4)") (class "Default")
      (node (ref "U2") (pin "L4") (pinfunction "PS_DDR_A6_502_L4") (pintype "passive"))
    )
    (net (code "216") (name "unconnected-(U2C-PS_DDR_A7_502-PadK4)") (class "Default")
      (node (ref "U2") (pin "K4") (pinfunction "PS_DDR_A7_502_K4") (pintype "passive"))
    )
    (net (code "217") (name "unconnected-(U2C-PS_DDR_A8_502-PadK1)") (class "Default")
      (node (ref "U2") (pin "K1") (pinfunction "PS_DDR_A8_502_K1") (pintype "passive"))
    )
    (net (code "218") (name "unconnected-(U2C-PS_DDR_A9_502-PadJ4)") (class "Default")
      (node (ref "U2") (pin "J4") (pinfunction "PS_DDR_A9_502_J4") (pintype "passive"))
    )
    (net (code "219") (name "unconnected-(U2C-PS_DDR_A10_502-PadF5)") (class "Default")
      (node (ref "U2") (pin "F5") (pinfunction "PS_DDR_A10_502_F5") (pintype "passive"))
    )
    (net (code "220") (name "unconnected-(U2C-PS_DDR_A11_502-PadG4)") (class "Default")
      (node (ref "U2") (pin "G4") (pinfunction "PS_DDR_A11_502_G4") (pintype "passive"))
    )
    (net (code "221") (name "unconnected-(U2C-PS_DDR_A12_502-PadE4)") (class "Default")
      (node (ref "U2") (pin "E4") (pinfunction "PS_DDR_A12_502_E4") (pintype "passive"))
    )
    (net (code "222") (name "unconnected-(U2C-PS_DDR_A13_502-PadD4)") (class "Default")
      (node (ref "U2") (pin "D4") (pinfunction "PS_DDR_A13_502_D4") (pintype "passive"))
    )
    (net (code "223") (name "unconnected-(U2C-PS_DDR_A14_502-PadF4)") (class "Default")
      (node (ref "U2") (pin "F4") (pinfunction "PS_DDR_A14_502_F4") (pintype "passive"))
    )
    (net (code "224") (name "unconnected-(U2C-PS_DDR_BA0_502-PadL5)") (class "Default")
      (node (ref "U2") (pin "L5") (pinfunction "PS_DDR_BA0_502_L5") (pintype "passive"))
    )
    (net (code "225") (name "unconnected-(U2C-PS_DDR_BA1_502-PadR4)") (class "Default")
      (node (ref "U2") (pin "R4") (pinfunction "PS_DDR_BA1_502_R4") (pintype "passive"))
    )
    (net (code "226") (name "unconnected-(U2C-PS_DDR_BA2_502-PadJ5)") (class "Default")
      (node (ref "U2") (pin "J5") (pinfunction "PS_DDR_BA2_502_J5") (pintype "passive"))
    )
    (net (code "227") (name "unconnected-(U2C-PS_DDR_CAS_B_502-PadP5)") (class "Default")
      (node (ref "U2") (pin "P5") (pinfunction "PS_DDR_CAS_B_502_P5") (pintype "passive"))
    )
    (net (code "228") (name "unconnected-(U2C-PS_DDR_CKE_502-PadN3)") (class "Default")
      (node (ref "U2") (pin "N3") (pinfunction "PS_DDR_CKE_502_N3") (pintype "passive"))
    )
    (net (code "229") (name "unconnected-(U2C-PS_DDR_CKN_502-PadM2)") (class "Default")
      (node (ref "U2") (pin "M2") (pinfunction "PS_DDR_CKN_502_M2") (pintype "passive"))
    )
    (net (code "230") (name "unconnected-(U2C-PS_DDR_CKP_502-PadL2)") (class "Default")
      (node (ref "U2") (pin "L2") (pinfunction "PS_DDR_CKP_502_L2") (pintype "passive"))
    )
    (net (code "231") (name "unconnected-(U2C-PS_DDR_CS_B_502-PadN1)") (class "Default")
      (node (ref "U2") (pin "N1") (pinfunction "PS_DDR_CS_B_502_N1") (pintype "passive"))
    )
    (net (code "232") (name "unconnected-(U2C-PS_DDR_DM0_502-PadA1)") (class "Default")
      (node (ref "U2") (pin "A1") (pinfunction "PS_DDR_DM0_502_A1") (pintype "passive"))
    )
    (net (code "233") (name "unconnected-(U2C-PS_DDR_DM1_502-PadF1)") (class "Default")
      (node (ref "U2") (pin "F1") (pinfunction "PS_DDR_DM1_502_F1") (pintype "passive"))
    )
    (net (code "234") (name "unconnected-(U2C-PS_DDR_DM2_502-PadT1)") (class "Default")
      (node (ref "U2") (pin "T1") (pinfunction "PS_DDR_DM2_502_T1") (pintype "passive"))
    )
    (net (code "235") (name "unconnected-(U2C-PS_DDR_DM3_502-PadY1)") (class "Default")
      (node (ref "U2") (pin "Y1") (pinfunction "PS_DDR_DM3_502_Y1") (pintype "passive"))
    )
    (net (code "236") (name "unconnected-(U2C-PS_DDR_DQ0_502-PadC3)") (class "Default")
      (node (ref "U2") (pin "C3") (pinfunction "PS_DDR_DQ0_502_C3") (pintype "passive"))
    )
    (net (code "237") (name "unconnected-(U2C-PS_DDR_DQ1_502-PadB3)") (class "Default")
      (node (ref "U2") (pin "B3") (pinfunction "PS_DDR_DQ1_502_B3") (pintype "passive"))
    )
    (net (code "238") (name "unconnected-(U2C-PS_DDR_DQ2_502-PadA2)") (class "Default")
      (node (ref "U2") (pin "A2") (pinfunction "PS_DDR_DQ2_502_A2") (pintype "passive"))
    )
    (net (code "239") (name "unconnected-(U2C-PS_DDR_DQ3_502-PadA4)") (class "Default")
      (node (ref "U2") (pin "A4") (pinfunction "PS_DDR_DQ3_502_A4") (pintype "passive"))
    )
    (net (code "240") (name "unconnected-(U2C-PS_DDR_DQ4_502-PadD3)") (class "Default")
      (node (ref "U2") (pin "D3") (pinfunction "PS_DDR_DQ4_502_D3") (pintype "passive"))
    )
    (net (code "241") (name "unconnected-(U2C-PS_DDR_DQ5_502-PadD1)") (class "Default")
      (node (ref "U2") (pin "D1") (pinfunction "PS_DDR_DQ5_502_D1") (pintype "passive"))
    )
    (net (code "242") (name "unconnected-(U2C-PS_DDR_DQ6_502-PadC1)") (class "Default")
      (node (ref "U2") (pin "C1") (pinfunction "PS_DDR_DQ6_502_C1") (pintype "passive"))
    )
    (net (code "243") (name "unconnected-(U2C-PS_DDR_DQ7_502-PadE1)") (class "Default")
      (node (ref "U2") (pin "E1") (pinfunction "PS_DDR_DQ7_502_E1") (pintype "passive"))
    )
    (net (code "244") (name "unconnected-(U2C-PS_DDR_DQ8_502-PadE2)") (class "Default")
      (node (ref "U2") (pin "E2") (pinfunction "PS_DDR_DQ8_502_E2") (pintype "passive"))
    )
    (net (code "245") (name "unconnected-(U2C-PS_DDR_DQ9_502-PadE3)") (class "Default")
      (node (ref "U2") (pin "E3") (pinfunction "PS_DDR_DQ9_502_E3") (pintype "passive"))
    )
    (net (code "246") (name "unconnected-(U2C-PS_DDR_DQ10_502-PadG3)") (class "Default")
      (node (ref "U2") (pin "G3") (pinfunction "PS_DDR_DQ10_502_G3") (pintype "passive"))
    )
    (net (code "247") (name "unconnected-(U2C-PS_DDR_DQ11_502-PadH3)") (class "Default")
      (node (ref "U2") (pin "H3") (pinfunction "PS_DDR_DQ11_502_H3") (pintype "passive"))
    )
    (net (code "248") (name "unconnected-(U2C-PS_DDR_DQ12_502-PadJ3)") (class "Default")
      (node (ref "U2") (pin "J3") (pinfunction "PS_DDR_DQ12_502_J3") (pintype "passive"))
    )
    (net (code "249") (name "unconnected-(U2C-PS_DDR_DQ13_502-PadH2)") (class "Default")
      (node (ref "U2") (pin "H2") (pinfunction "PS_DDR_DQ13_502_H2") (pintype "passive"))
    )
    (net (code "250") (name "unconnected-(U2C-PS_DDR_DQ14_502-PadH1)") (class "Default")
      (node (ref "U2") (pin "H1") (pinfunction "PS_DDR_DQ14_502_H1") (pintype "passive"))
    )
    (net (code "251") (name "unconnected-(U2C-PS_DDR_DQ15_502-PadJ1)") (class "Default")
      (node (ref "U2") (pin "J1") (pinfunction "PS_DDR_DQ15_502_J1") (pintype "passive"))
    )
    (net (code "252") (name "unconnected-(U2C-PS_DDR_DQ16_502-PadP1)") (class "Default")
      (node (ref "U2") (pin "P1") (pinfunction "PS_DDR_DQ16_502_P1") (pintype "passive"))
    )
    (net (code "253") (name "unconnected-(U2C-PS_DDR_DQ17_502-PadP3)") (class "Default")
      (node (ref "U2") (pin "P3") (pinfunction "PS_DDR_DQ17_502_P3") (pintype "passive"))
    )
    (net (code "254") (name "unconnected-(U2C-PS_DDR_DQ18_502-PadR3)") (class "Default")
      (node (ref "U2") (pin "R3") (pinfunction "PS_DDR_DQ18_502_R3") (pintype "passive"))
    )
    (net (code "255") (name "unconnected-(U2C-PS_DDR_DQ19_502-PadR1)") (class "Default")
      (node (ref "U2") (pin "R1") (pinfunction "PS_DDR_DQ19_502_R1") (pintype "passive"))
    )
    (net (code "256") (name "unconnected-(U2C-PS_DDR_DQ20_502-PadT4)") (class "Default")
      (node (ref "U2") (pin "T4") (pinfunction "PS_DDR_DQ20_502_T4") (pintype "passive"))
    )
    (net (code "257") (name "unconnected-(U2C-PS_DDR_DQ21_502-PadU4)") (class "Default")
      (node (ref "U2") (pin "U4") (pinfunction "PS_DDR_DQ21_502_U4") (pintype "passive"))
    )
    (net (code "258") (name "unconnected-(U2C-PS_DDR_DQ22_502-PadU2)") (class "Default")
      (node (ref "U2") (pin "U2") (pinfunction "PS_DDR_DQ22_502_U2") (pintype "passive"))
    )
    (net (code "259") (name "unconnected-(U2C-PS_DDR_DQ23_502-PadU3)") (class "Default")
      (node (ref "U2") (pin "U3") (pinfunction "PS_DDR_DQ23_502_U3") (pintype "passive"))
    )
    (net (code "260") (name "unconnected-(U2C-PS_DDR_DQ24_502-PadV1)") (class "Default")
      (node (ref "U2") (pin "V1") (pinfunction "PS_DDR_DQ24_502_V1") (pintype "passive"))
    )
    (net (code "261") (name "unconnected-(U2C-PS_DDR_DQ25_502-PadY3)") (class "Default")
      (node (ref "U2") (pin "Y3") (pinfunction "PS_DDR_DQ25_502_Y3") (pintype "passive"))
    )
    (net (code "262") (name "unconnected-(U2C-PS_DDR_DQ26_502-PadW1)") (class "Default")
      (node (ref "U2") (pin "W1") (pinfunction "PS_DDR_DQ26_502_W1") (pintype "passive"))
    )
    (net (code "263") (name "unconnected-(U2C-PS_DDR_DQ27_502-PadY4)") (class "Default")
      (node (ref "U2") (pin "Y4") (pinfunction "PS_DDR_DQ27_502_Y4") (pintype "passive"))
    )
    (net (code "264") (name "unconnected-(U2C-PS_DDR_DQ28_502-PadY2)") (class "Default")
      (node (ref "U2") (pin "Y2") (pinfunction "PS_DDR_DQ28_502_Y2") (pintype "passive"))
    )
    (net (code "265") (name "unconnected-(U2C-PS_DDR_DQ29_502-PadW3)") (class "Default")
      (node (ref "U2") (pin "W3") (pinfunction "PS_DDR_DQ29_502_W3") (pintype "passive"))
    )
    (net (code "266") (name "unconnected-(U2C-PS_DDR_DQ30_502-PadV2)") (class "Default")
      (node (ref "U2") (pin "V2") (pinfunction "PS_DDR_DQ30_502_V2") (pintype "passive"))
    )
    (net (code "267") (name "unconnected-(U2C-PS_DDR_DQ31_502-PadV3)") (class "Default")
      (node (ref "U2") (pin "V3") (pinfunction "PS_DDR_DQ31_502_V3") (pintype "passive"))
    )
    (net (code "268") (name "unconnected-(U2C-PS_DDR_DQS_N0_502-PadB2)") (class "Default")
      (node (ref "U2") (pin "B2") (pinfunction "PS_DDR_DQS_N0_502_B2") (pintype "passive"))
    )
    (net (code "269") (name "unconnected-(U2C-PS_DDR_DQS_N1_502-PadF2)") (class "Default")
      (node (ref "U2") (pin "F2") (pinfunction "PS_DDR_DQS_N1_502_F2") (pintype "passive"))
    )
    (net (code "270") (name "unconnected-(U2C-PS_DDR_DQS_N2_502-PadT2)") (class "Default")
      (node (ref "U2") (pin "T2") (pinfunction "PS_DDR_DQS_N2_502_T2") (pintype "passive"))
    )
    (net (code "271") (name "unconnected-(U2C-PS_DDR_DQS_N3_502-PadW4)") (class "Default")
      (node (ref "U2") (pin "W4") (pinfunction "PS_DDR_DQS_N3_502_W4") (pintype "passive"))
    )
    (net (code "272") (name "unconnected-(U2C-PS_DDR_DQS_P0_502-PadC2)") (class "Default")
      (node (ref "U2") (pin "C2") (pinfunction "PS_DDR_DQS_P0_502_C2") (pintype "passive"))
    )
    (net (code "273") (name "unconnected-(U2C-PS_DDR_DQS_P1_502-PadG2)") (class "Default")
      (node (ref "U2") (pin "G2") (pinfunction "PS_DDR_DQS_P1_502_G2") (pintype "passive"))
    )
    (net (code "274") (name "unconnected-(U2C-PS_DDR_DQS_P2_502-PadR2)") (class "Default")
      (node (ref "U2") (pin "R2") (pinfunction "PS_DDR_DQS_P2_502_R2") (pintype "passive"))
    )
    (net (code "275") (name "unconnected-(U2C-PS_DDR_DQS_P3_502-PadW5)") (class "Default")
      (node (ref "U2") (pin "W5") (pinfunction "PS_DDR_DQS_P3_502_W5") (pintype "passive"))
    )
    (net (code "276") (name "unconnected-(U2C-PS_DDR_DRST_B_502-PadB4)") (class "Default")
      (node (ref "U2") (pin "B4") (pinfunction "PS_DDR_DRST_B_502_B4") (pintype "passive"))
    )
    (net (code "277") (name "unconnected-(U2C-PS_DDR_ODT_502-PadN5)") (class "Default")
      (node (ref "U2") (pin "N5") (pinfunction "PS_DDR_ODT_502_N5") (pintype "passive"))
    )
    (net (code "278") (name "unconnected-(U2C-PS_DDR_RAS_B_502-PadP4)") (class "Default")
      (node (ref "U2") (pin "P4") (pinfunction "PS_DDR_RAS_B_502_P4") (pintype "passive"))
    )
    (net (code "279") (name "unconnected-(U2C-PS_DDR_VRN_502-PadG5)") (class "Default")
      (node (ref "U2") (pin "G5") (pinfunction "PS_DDR_VRN_502_G5") (pintype "passive"))
    )
    (net (code "280") (name "unconnected-(U2C-PS_DDR_VRP_502-PadH5)") (class "Default")
      (node (ref "U2") (pin "H5") (pinfunction "PS_DDR_VRP_502_H5") (pintype "passive"))
    )
    (net (code "281") (name "unconnected-(U2C-PS_DDR_WE_B_502-PadM5)") (class "Default")
      (node (ref "U2") (pin "M5") (pinfunction "PS_DDR_WE_B_502_M5") (pintype "passive"))
    )
  )
)
